# Modular_RFPA_RevB.net
KiCad netlist of a schematic drawn in EAGLE
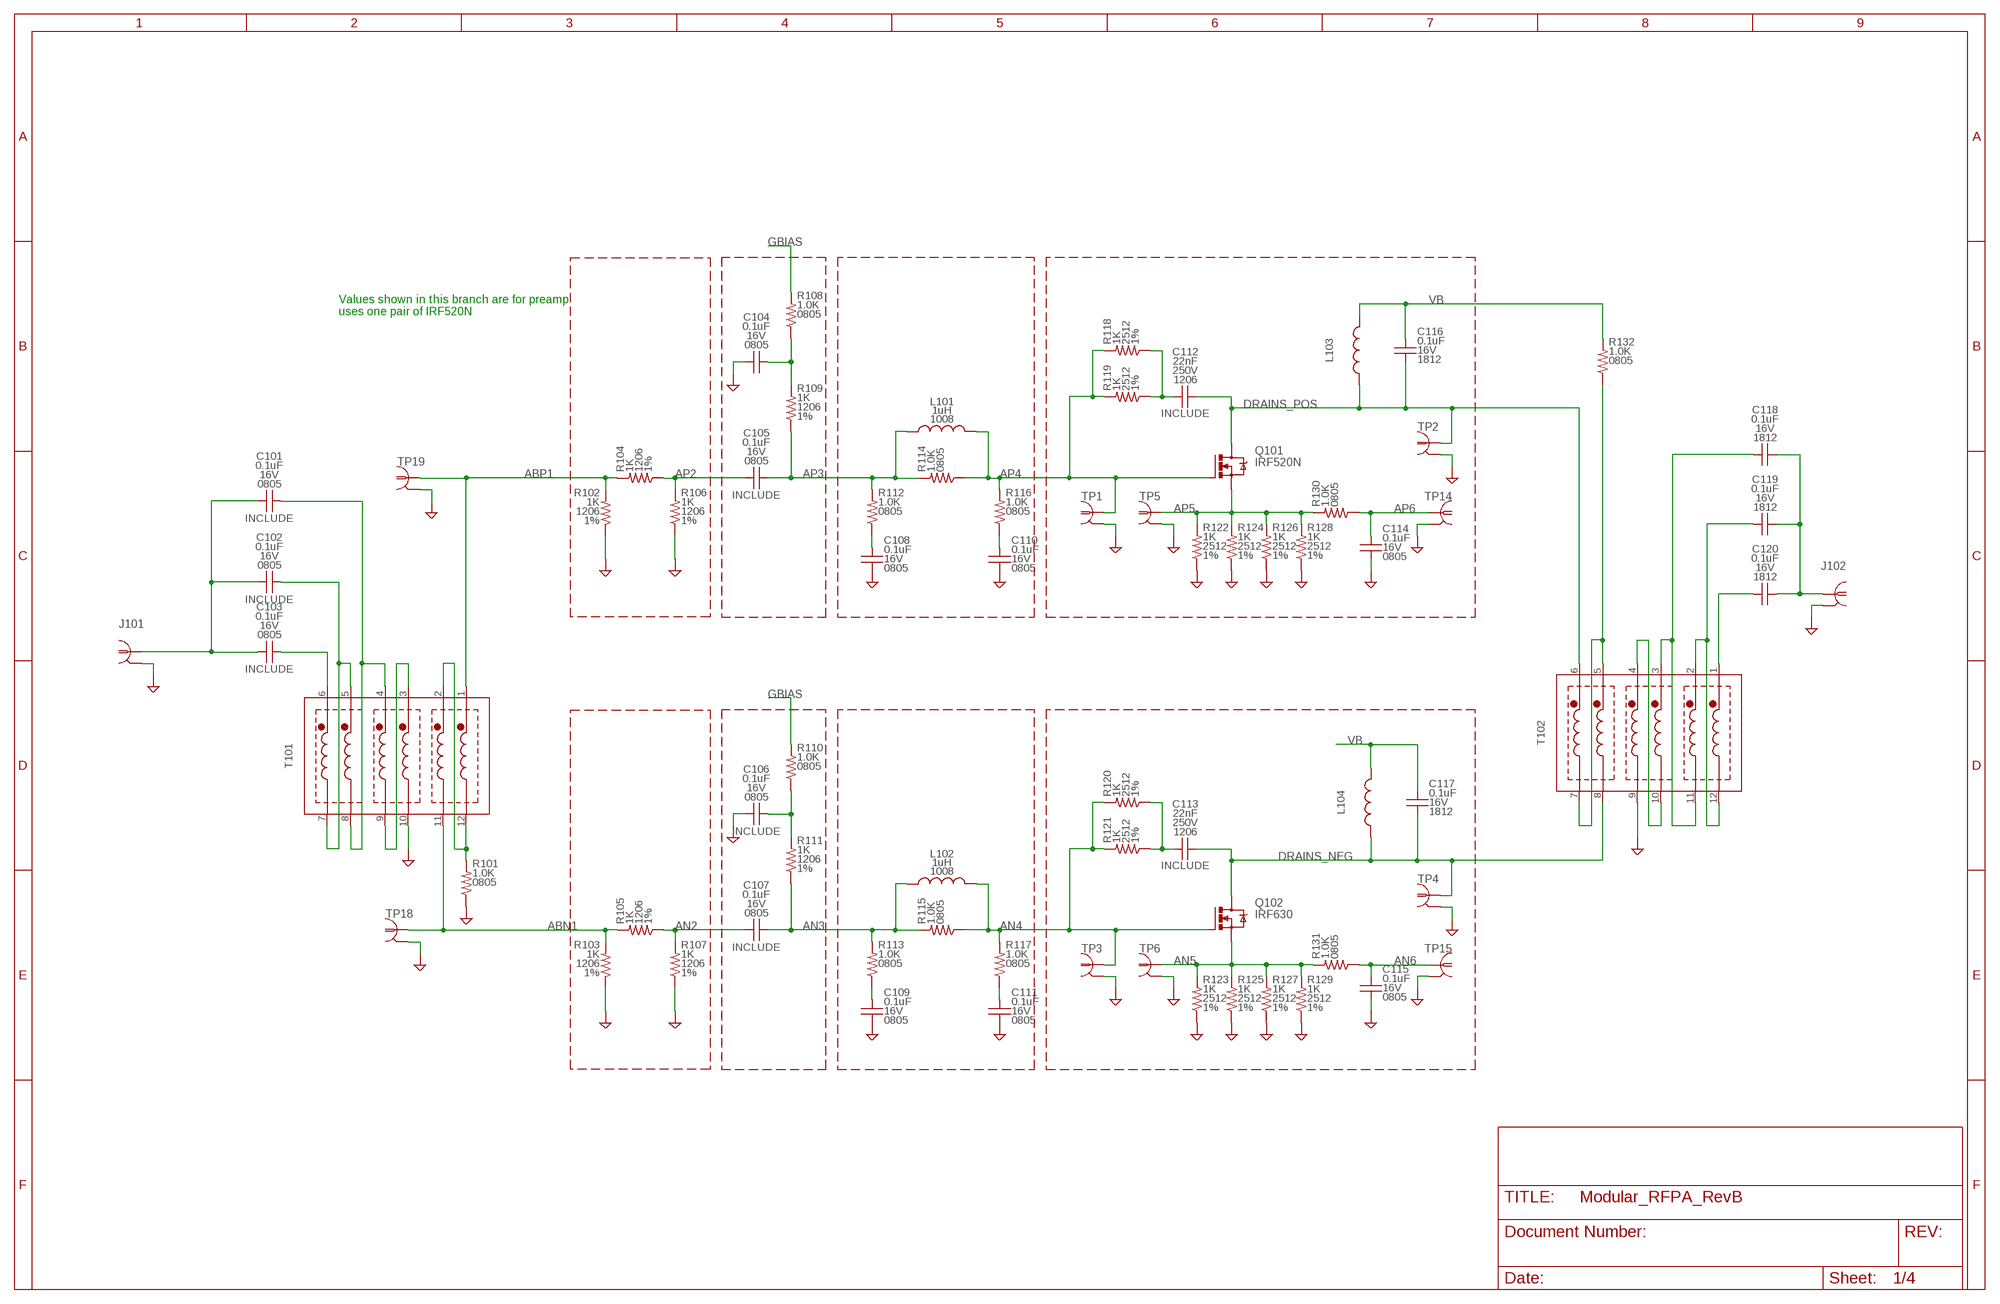
[diagram p0: schematic, sheet 1, part 1 of 2]
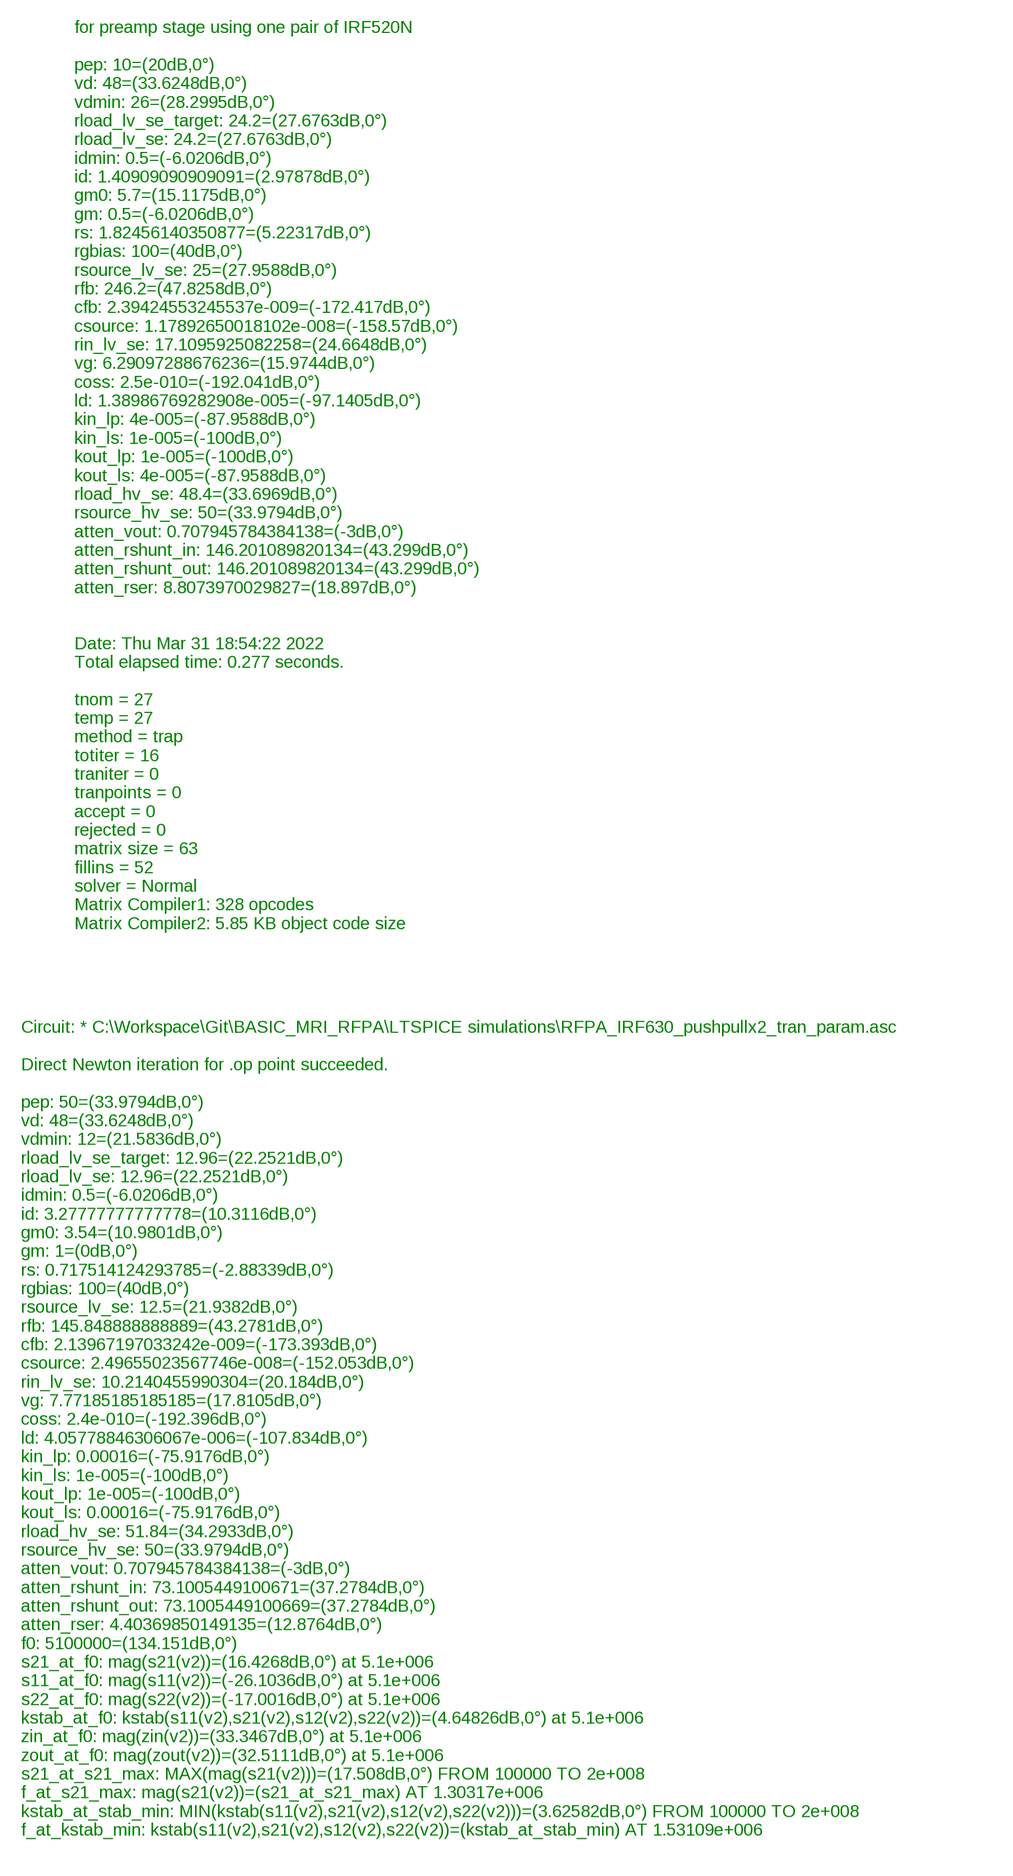
[diagram p1: schematic, sheet 1, part 2 of 2]
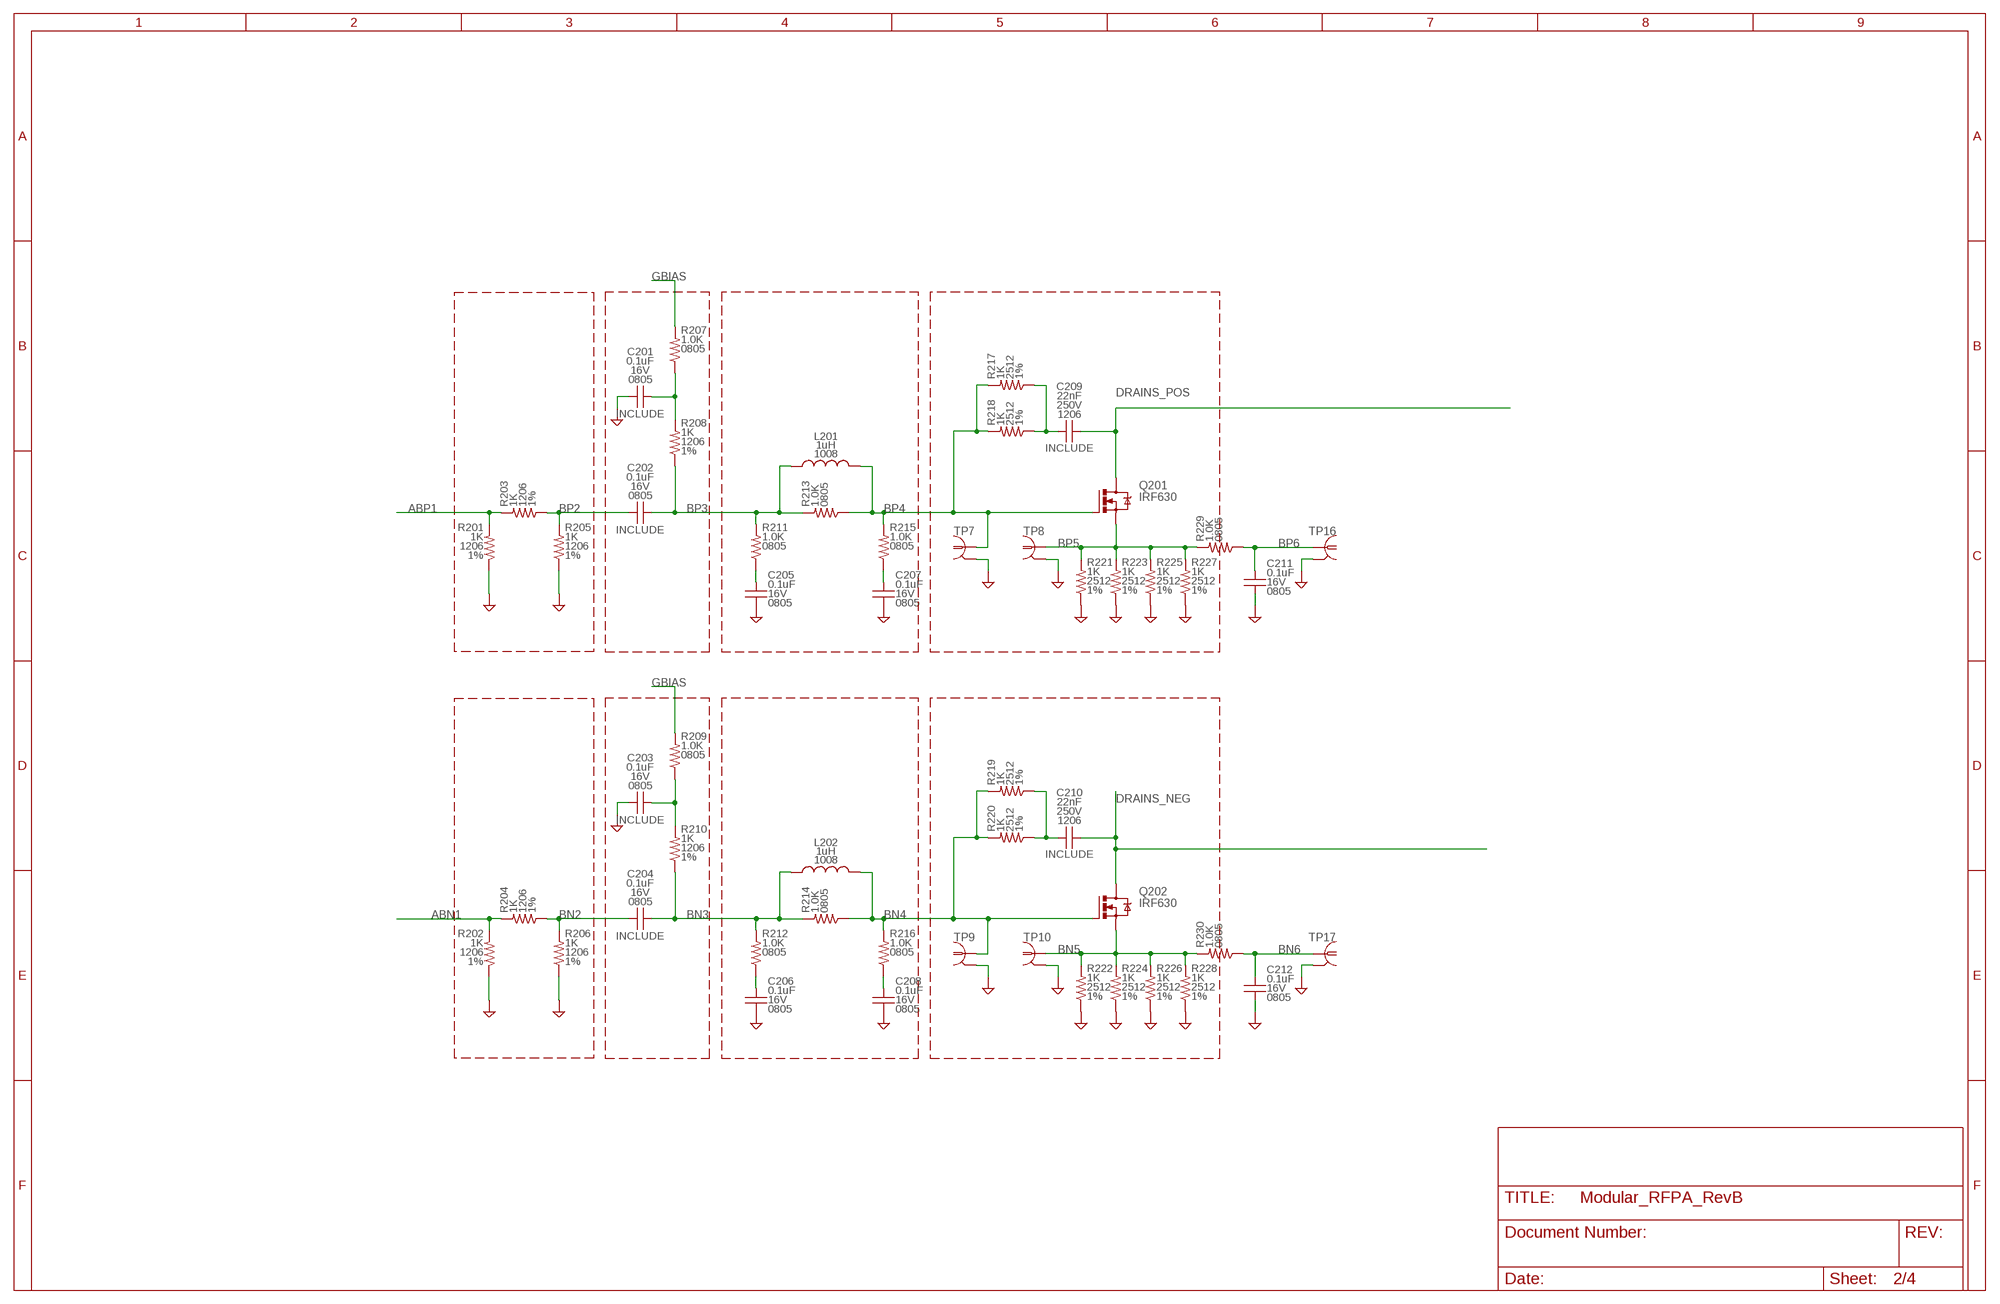
[diagram p2: schematic, sheet 2]
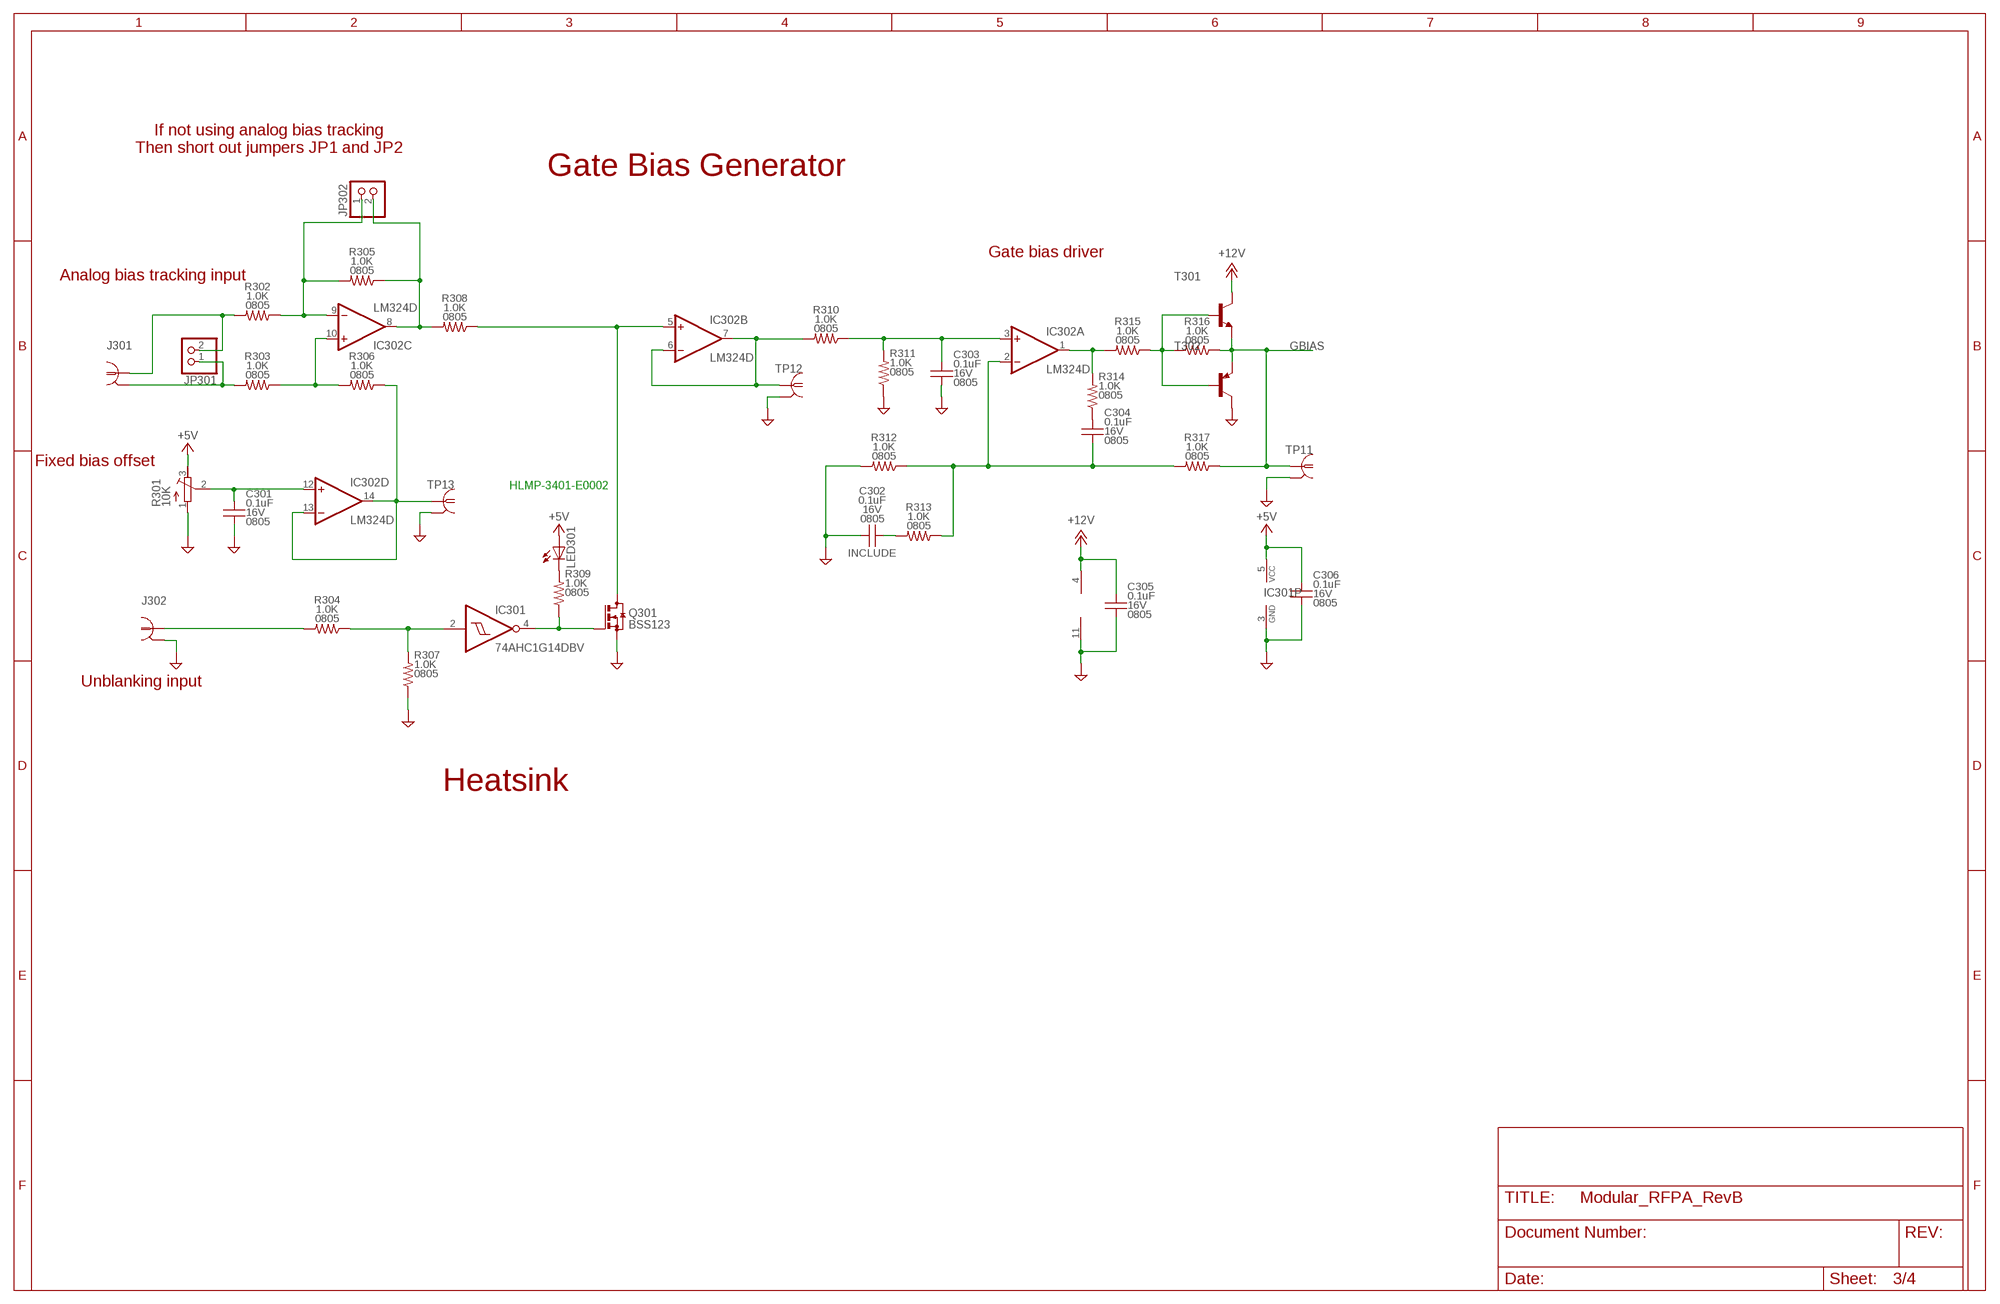
[diagram p3: schematic, sheet 3]
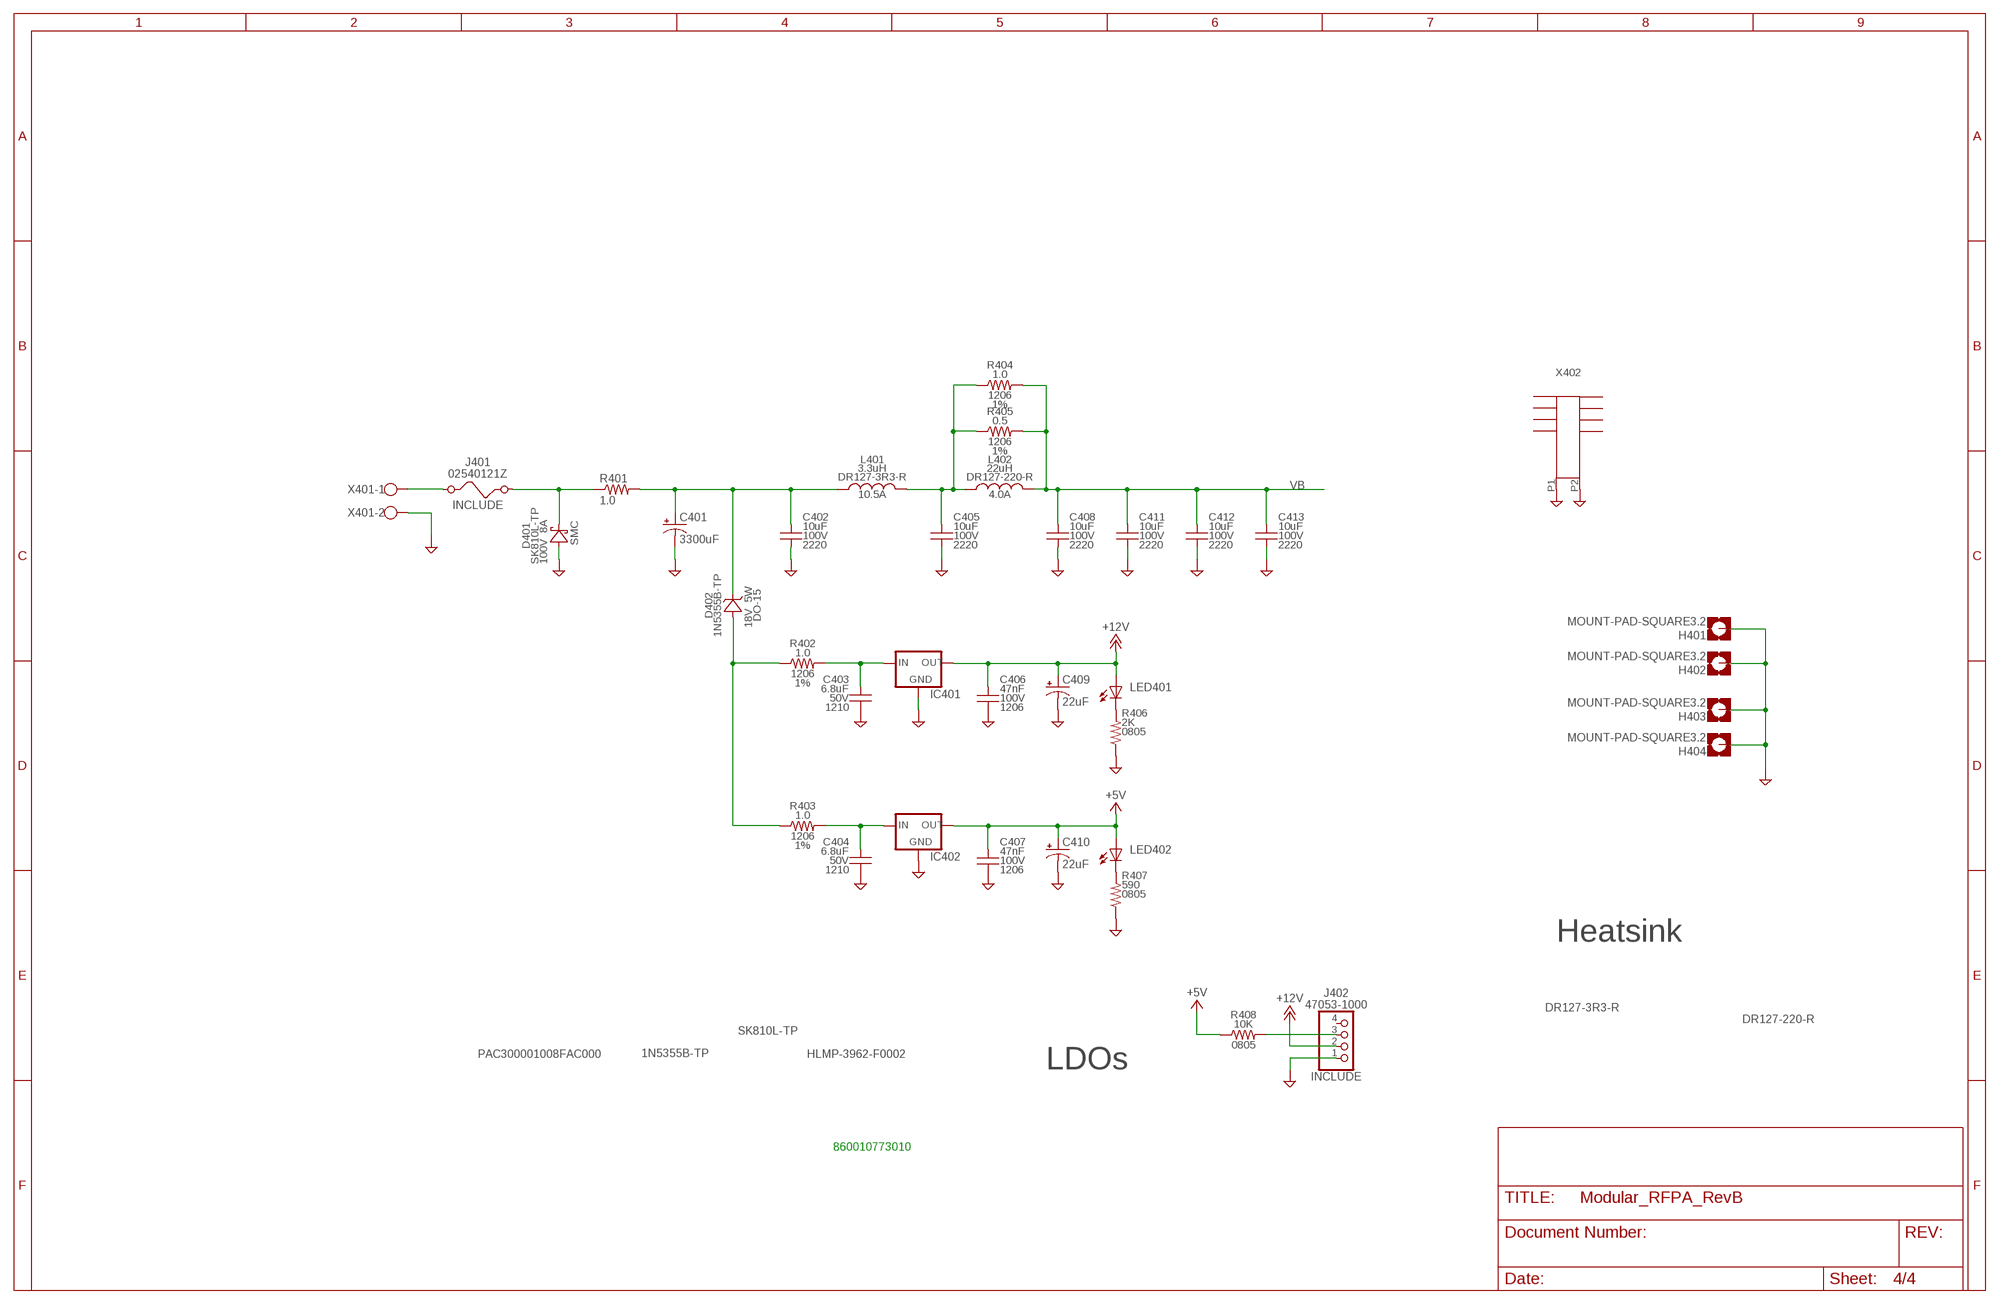
[diagram p4: schematic, sheet 4]

(export (version "E")
  (design (tool "Eeschema 10.0.6"))
  (components
    (comp (ref "C401")
      (value "3300uF")
      (footprint "eagle-import:EB25D")
      (libsource (lib "eagle-import") (part "CPOL-USE10-25"))
    )
    (comp (ref "C402")
      (value "10uF")
      (footprint "eagle-import:C2220_CKG57N")
      (fields
        (field (name "BOM") "INCLUDE")
        (field (name "PACKAGE") "2220")
        (field (name "PARTNO") "CGA9N3X7S2A106M230KE")
        (field (name "VOLTAGE") "100V")
      )
      (libsource (lib "eagle-import") (part "CC2220_CKG57NCC-10U-100V-20%-2220-X7T"))
    )
    (comp (ref "C403")
      (value "6.8uF")
      (footprint "eagle-import:C1210")
      (fields (field (name "PARTNO") "CGA6P3X7S1H685K250AB") (field (name "VOLTAGE") "50V"))
      (libsource (lib "eagle-import") (part "CC1210CC-6.8U-50V-10%-1210-X7S"))
    )
    (comp (ref "C404")
      (value "6.8uF")
      (footprint "eagle-import:C1210")
      (fields (field (name "PARTNO") "CGA6P3X7S1H685K250AB") (field (name "VOLTAGE") "50V"))
      (libsource (lib "eagle-import") (part "CC1210CC-6.8U-50V-10%-1210-X7S"))
    )
    (comp (ref "C405")
      (value "10uF")
      (footprint "eagle-import:C2220_CKG57N")
      (fields
        (field (name "BOM") "INCLUDE")
        (field (name "PACKAGE") "2220")
        (field (name "PARTNO") "CGA9N3X7S2A106M230KE")
        (field (name "VOLTAGE") "100V")
      )
      (libsource (lib "eagle-import") (part "CC2220_CKG57NCC-10U-100V-20%-2220-X7T"))
    )
    (comp (ref "C406")
      (value "47nF")
      (footprint "eagle-import:C1206")
      (fields (field (name "PARTNO") "C3216C0G2A473J115AC") (field (name "VOLTAGE") "100V"))
      (libsource (lib "eagle-import") (part "CC1206C-47N-100V-5%-1206-NP0"))
    )
    (comp (ref "C407")
      (value "47nF")
      (footprint "eagle-import:C1206")
      (fields (field (name "PARTNO") "C3216C0G2A473J115AC") (field (name "VOLTAGE") "100V"))
      (libsource (lib "eagle-import") (part "CC1206C-47N-100V-5%-1206-NP0"))
    )
    (comp (ref "C408")
      (value "10uF")
      (footprint "eagle-import:C2220_CKG57N")
      (fields (field (name "PARTNO") "CGA9N3X7S2A106M230KE") (field (name "VOLTAGE") "100V"))
      (libsource (lib "eagle-import") (part "CC2220_CKG57NCC-10U-100V-20%-2220-X7T"))
    )
    (comp (ref "C409")
      (value "22uF")
      (footprint "eagle-import:E2,5-7")
      (libsource (lib "eagle-import") (part "CPOL-USE2.5-7"))
    )
    (comp (ref "C410")
      (value "22uF")
      (footprint "eagle-import:E2,5-7")
      (libsource (lib "eagle-import") (part "CPOL-USE2.5-7"))
    )
    (comp (ref "C411")
      (value "10uF")
      (footprint "eagle-import:C2220_CKG57N")
      (fields (field (name "PARTNO") "CGA9N3X7S2A106M230KE") (field (name "VOLTAGE") "100V"))
      (libsource (lib "eagle-import") (part "CC2220_CKG57NCC-10U-100V-20%-2220-X7T"))
    )
    (comp (ref "C412")
      (value "10uF")
      (footprint "eagle-import:C2220_CKG57N")
      (fields (field (name "PARTNO") "CGA9N3X7S2A106M230KE") (field (name "VOLTAGE") "100V"))
      (libsource (lib "eagle-import") (part "CC2220_CKG57NCC-10U-100V-20%-2220-X7T"))
    )
    (comp (ref "C413")
      (value "10uF")
      (footprint "eagle-import:C2220_CKG57N")
      (fields (field (name "PARTNO") "CGA9N3X7S2A106M230KE") (field (name "VOLTAGE") "100V"))
      (libsource (lib "eagle-import") (part "CC2220_CKG57NCC-10U-100V-20%-2220-X7T"))
    )
    (comp (ref "D401")
      (value "D-SCHOTTKYSK810L-TPSMC")
      (footprint "eagle-import:DO-214AB(SMC)")
      (fields (field (name "PARTNO") "SK810L-TP") (field (name "VOLTAGE") "100V"))
      (libsource (lib "eagle-import") (part "D-SCHOTTKYSMCSK810L-TP"))
    )
    (comp (ref "D402")
      (value "D-ZENER1N5355B-TPDO15-12")
      (footprint "eagle-import:DO15-12")
      (fields (field (name "PARTNO") "1N5355B-TP") (field (name "POWER") "5W") (field (name "VOLTAGE") "18V"))
      (libsource (lib "eagle-import") (part "D-ZENERDO15-121N5355B-TP"))
    )
    (comp (ref "H401")
      (value "MOUNT-PAD-SQUARE3.2")
      (footprint "eagle-import:3,2-PAD-SQUARE")
      (libsource (lib "eagle-import") (part "MOUNT-PAD-SQUARE3.2"))
    )
    (comp (ref "H402")
      (value "MOUNT-PAD-SQUARE3.2")
      (footprint "eagle-import:3,2-PAD-SQUARE")
      (libsource (lib "eagle-import") (part "MOUNT-PAD-SQUARE3.2"))
    )
    (comp (ref "H403")
      (value "MOUNT-PAD-SQUARE3.2")
      (footprint "eagle-import:3,2-PAD-SQUARE")
      (libsource (lib "eagle-import") (part "MOUNT-PAD-SQUARE3.2"))
    )
    (comp (ref "H404")
      (value "MOUNT-PAD-SQUARE3.2")
      (footprint "eagle-import:3,2-PAD-SQUARE")
      (libsource (lib "eagle-import") (part "MOUNT-PAD-SQUARE3.2"))
    )
    (comp (ref "IC401")
      (value "78XXS")
      (footprint "eagle-import:78XXS")
      (libsource (lib "eagle-import") (part "78XXS"))
    )
    (comp (ref "IC402")
      (value "78XXS")
      (footprint "eagle-import:78XXS")
      (libsource (lib "eagle-import") (part "78XXS"))
    )
    (comp (ref "J401")
      (value "FUSE_2P")
      (footprint "eagle-import:02540121Z")
      (fields (field (name "PARTNO") "02540121Z"))
      (libsource (lib "eagle-import") (part "FUSE_2P"))
    )
    (comp (ref "J402")
      (value "KK_PCFAN")
      (footprint "eagle-import:47053-1000")
      (fields (field (name "PARTNO") "47053-1000"))
      (libsource (lib "eagle-import") (part "KK_PCFAN"))
    )
    (comp (ref "L401")
      (value "3.3uH")
      (footprint "eagle-import:DR127")
      (fields (field (name "PARTNO") "DR127-3R3-R"))
      (libsource (lib "eagle-import") (part "LL-3.3U-FERRITE-20%-12.5X12.5MM-10.5A"))
    )
    (comp (ref "L402")
      (value "22uH")
      (footprint "eagle-import:DR127")
      (fields (field (name "PARTNO") "DR127-220-R"))
      (libsource (lib "eagle-import") (part "LL-22U-FERRITE-20%-12.5X12.5MM-4A"))
    )
    (comp (ref "LED401")
      (value "LED5MM")
      (footprint "eagle-import:LED5MM")
      (libsource (lib "eagle-import") (part "LED5MM"))
    )
    (comp (ref "LED402")
      (value "LED5MM")
      (footprint "eagle-import:LED5MM")
      (libsource (lib "eagle-import") (part "LED5MM"))
    )
    (comp (ref "R401")
      (value "1.0")
      (footprint "eagle-import:P0817V")
      (libsource (lib "eagle-import") (part "R-US_0817/7V"))
    )
    (comp (ref "R402")
      (value "1.0")
      (footprint "eagle-import:R1206")
      (fields (field (name "POWER") "0.25"))
      (libsource (lib "eagle-import") (part "R90R1206R-1.0K-1%-1206-0.25W"))
    )
    (comp (ref "R403")
      (value "1.0")
      (footprint "eagle-import:R1206")
      (fields (field (name "POWER") "0.25"))
      (libsource (lib "eagle-import") (part "R90R1206R-1.0K-1%-1206-0.25W"))
    )
    (comp (ref "R404")
      (value "1.0")
      (footprint "eagle-import:R1206")
      (fields (field (name "POWER") "0.25"))
      (libsource (lib "eagle-import") (part "R90R1206R-1.0K-1%-1206-0.25W"))
    )
    (comp (ref "R405")
      (value "0.5")
      (footprint "eagle-import:R1206")
      (fields (field (name "POWER") "0.25"))
      (libsource (lib "eagle-import") (part "R90R1206R-1.0K-1%-1206-0.25W"))
    )
    (comp (ref "R406")
      (value "2K")
      (footprint "eagle-import:0805_IPC-7351B")
      (libsource (lib "eagle-import") (part "R0805_IPCR-1.0K-0.1%-0805-0.1W"))
    )
    (comp (ref "R407")
      (value "590")
      (footprint "eagle-import:0805_IPC-7351B")
      (libsource (lib "eagle-import") (part "R0805_IPCR-1.0K-0.1%-0805-0.1W"))
    )
    (comp (ref "R408")
      (value "10K")
      (footprint "eagle-import:0805_IPC-7351B")
      (libsource (lib "eagle-import") (part "R900805_IPCR-1.0K-0.1%-0805-0.1W"))
    )
    (comp (ref "X401")
      (value "W237-102")
      (footprint "eagle-import:W237-102")
      (fields (field (name "MPN") "237-102"))
      (libsource (lib "eagle-import") (part "W237-102"))
    )
    (comp (ref "X402")
      (value "HEATSINK_OMNI_DUAL30-75-D")
      (footprint "eagle-import:OMNI-UNI-30-75-D")
      (libsource (lib "eagle-import") (part "HEATSINK_OMNI_DUAL30-75-D"))
    )
    (comp (ref "C201")
      (value "0.1uF")
      (footprint "eagle-import:0805_IPC-7351B")
      (fields (field (name "PACKAGE") "0805") (field (name "VOLTAGE") "16V") (field (name "BOM") "INCLUDE"))
      (libsource (lib "eagle-import") (part "C0805_IPCC-0.1U-16V-0805-X7R"))
    )
    (comp (ref "C202")
      (value "0.1uF")
      (footprint "eagle-import:0805_IPC-7351B")
      (fields (field (name "PACKAGE") "0805") (field (name "VOLTAGE") "16V") (field (name "BOM") "INCLUDE"))
      (libsource (lib "eagle-import") (part "C0805_IPCC-0.1U-16V-0805-X7R"))
    )
    (comp (ref "C203")
      (value "0.1uF")
      (footprint "eagle-import:0805_IPC-7351B")
      (fields (field (name "PACKAGE") "0805") (field (name "VOLTAGE") "16V") (field (name "BOM") "INCLUDE"))
      (libsource (lib "eagle-import") (part "C0805_IPCC-0.1U-16V-0805-X7R"))
    )
    (comp (ref "C204")
      (value "0.1uF")
      (footprint "eagle-import:0805_IPC-7351B")
      (fields (field (name "PACKAGE") "0805") (field (name "VOLTAGE") "16V") (field (name "BOM") "INCLUDE"))
      (libsource (lib "eagle-import") (part "C0805_IPCC-0.1U-16V-0805-X7R"))
    )
    (comp (ref "C205")
      (value "0.1uF")
      (footprint "eagle-import:0805_IPC-7351B")
      (fields (field (name "VOLTAGE") "16V"))
      (libsource (lib "eagle-import") (part "C0805_IPCC-0.1U-16V-0805-X7R"))
    )
    (comp (ref "C206")
      (value "0.1uF")
      (footprint "eagle-import:0805_IPC-7351B")
      (fields (field (name "VOLTAGE") "16V"))
      (libsource (lib "eagle-import") (part "C0805_IPCC-0.1U-16V-0805-X7R"))
    )
    (comp (ref "C207")
      (value "0.1uF")
      (footprint "eagle-import:0805_IPC-7351B")
      (fields (field (name "VOLTAGE") "16V"))
      (libsource (lib "eagle-import") (part "C0805_IPCC-0.1U-16V-0805-X7R"))
    )
    (comp (ref "C208")
      (value "0.1uF")
      (footprint "eagle-import:0805_IPC-7351B")
      (fields (field (name "VOLTAGE") "16V"))
      (libsource (lib "eagle-import") (part "C0805_IPCC-0.1U-16V-0805-X7R"))
    )
    (comp (ref "C209")
      (value "22nF")
      (footprint "eagle-import:C1206")
      (fields
        (field (name "BOM") "INCLUDE")
        (field (name "PACKAGE") "1206")
        (field (name "PARTNO") "C3216NP02E223J160AA")
        (field (name "VOLTAGE") "250V")
      )
      (libsource (lib "eagle-import") (part "CC1206C-22N-250V-5%-1206-NP0"))
    )
    (comp (ref "C210")
      (value "22nF")
      (footprint "eagle-import:C1206")
      (fields
        (field (name "BOM") "INCLUDE")
        (field (name "PACKAGE") "1206")
        (field (name "PARTNO") "C3216NP02E223J160AA")
        (field (name "VOLTAGE") "250V")
      )
      (libsource (lib "eagle-import") (part "CC1206C-22N-250V-5%-1206-NP0"))
    )
    (comp (ref "C211")
      (value "0.1uF")
      (footprint "eagle-import:0805_IPC-7351B")
      (fields (field (name "VOLTAGE") "16V"))
      (libsource (lib "eagle-import") (part "C0805_IPCC-0.1U-16V-0805-X7R"))
    )
    (comp (ref "C212")
      (value "0.1uF")
      (footprint "eagle-import:0805_IPC-7351B")
      (fields (field (name "VOLTAGE") "16V"))
      (libsource (lib "eagle-import") (part "C0805_IPCC-0.1U-16V-0805-X7R"))
    )
    (comp (ref "L201")
      (value "1uH")
      (footprint "eagle-import:L1008")
      (fields (field (name "PARTNO") "1008CS-102XJEC"))
      (libsource (lib "eagle-import") (part "L_CHIP1008L-1.0U-AIR-5%-1008-0.37A"))
    )
    (comp (ref "L202")
      (value "1uH")
      (footprint "eagle-import:L1008")
      (fields (field (name "PARTNO") "1008CS-102XJEC"))
      (libsource (lib "eagle-import") (part "L_CHIP1008L-1.0U-AIR-5%-1008-0.37A"))
    )
    (comp (ref "Q201")
      (value "IRF630")
      (footprint "eagle-import:TO220BV")
      (libsource (lib "eagle-import") (part "IRF540"))
    )
    (comp (ref "Q202")
      (value "IRF630")
      (footprint "eagle-import:TO220BV")
      (libsource (lib "eagle-import") (part "IRF540"))
    )
    (comp (ref "R201")
      (value "1K")
      (footprint "eagle-import:R1206")
      (fields (field (name "POWER") "0.25"))
      (libsource (lib "eagle-import") (part "RR1206R-1.0K-1%-1206-0.25W"))
    )
    (comp (ref "R202")
      (value "1K")
      (footprint "eagle-import:R1206")
      (fields (field (name "POWER") "0.25"))
      (libsource (lib "eagle-import") (part "RR1206R-1.0K-1%-1206-0.25W"))
    )
    (comp (ref "R203")
      (value "1K")
      (footprint "eagle-import:R1206")
      (fields (field (name "POWER") "0.25"))
      (libsource (lib "eagle-import") (part "RR1206R-1.0K-1%-1206-0.25W"))
    )
    (comp (ref "R204")
      (value "1K")
      (footprint "eagle-import:R1206")
      (fields (field (name "POWER") "0.25"))
      (libsource (lib "eagle-import") (part "RR1206R-1.0K-1%-1206-0.25W"))
    )
    (comp (ref "R205")
      (value "1K")
      (footprint "eagle-import:R1206")
      (fields (field (name "POWER") "0.25"))
      (libsource (lib "eagle-import") (part "RR1206R-1.0K-1%-1206-0.25W"))
    )
    (comp (ref "R206")
      (value "1K")
      (footprint "eagle-import:R1206")
      (fields (field (name "POWER") "0.25"))
      (libsource (lib "eagle-import") (part "RR1206R-1.0K-1%-1206-0.25W"))
    )
    (comp (ref "R207")
      (value "1.0K")
      (footprint "eagle-import:0805_IPC-7351B")
      (libsource (lib "eagle-import") (part "R0805_IPCR-1.0K-0.1%-0805-0.1W"))
    )
    (comp (ref "R208")
      (value "1K")
      (footprint "eagle-import:R1206")
      (fields (field (name "POWER") "0.25"))
      (libsource (lib "eagle-import") (part "RR1206R-1.0K-1%-1206-0.25W"))
    )
    (comp (ref "R209")
      (value "1.0K")
      (footprint "eagle-import:0805_IPC-7351B")
      (libsource (lib "eagle-import") (part "R0805_IPCR-1.0K-0.1%-0805-0.1W"))
    )
    (comp (ref "R210")
      (value "1K")
      (footprint "eagle-import:R1206")
      (fields (field (name "POWER") "0.25"))
      (libsource (lib "eagle-import") (part "RR1206R-1.0K-1%-1206-0.25W"))
    )
    (comp (ref "R211")
      (value "1.0K")
      (footprint "eagle-import:0805_IPC-7351B")
      (libsource (lib "eagle-import") (part "R0805_IPCR-1.0K-0.1%-0805-0.1W"))
    )
    (comp (ref "R212")
      (value "1.0K")
      (footprint "eagle-import:0805_IPC-7351B")
      (libsource (lib "eagle-import") (part "R0805_IPCR-1.0K-0.1%-0805-0.1W"))
    )
    (comp (ref "R213")
      (value "1.0K")
      (footprint "eagle-import:0805_IPC-7351B")
      (libsource (lib "eagle-import") (part "R0805_IPCR-1.0K-0.1%-0805-0.1W"))
    )
    (comp (ref "R214")
      (value "1.0K")
      (footprint "eagle-import:0805_IPC-7351B")
      (libsource (lib "eagle-import") (part "R0805_IPCR-1.0K-0.1%-0805-0.1W"))
    )
    (comp (ref "R215")
      (value "1.0K")
      (footprint "eagle-import:0805_IPC-7351B")
      (libsource (lib "eagle-import") (part "R0805_IPCR-1.0K-0.1%-0805-0.1W"))
    )
    (comp (ref "R216")
      (value "1.0K")
      (footprint "eagle-import:0805_IPC-7351B")
      (libsource (lib "eagle-import") (part "R0805_IPCR-1.0K-0.1%-0805-0.1W"))
    )
    (comp (ref "R217")
      (value "1K")
      (footprint "eagle-import:R2512")
      (fields (field (name "POWER") "1"))
      (libsource (lib "eagle-import") (part "RR2512R-1K-1%-2512-1W"))
    )
    (comp (ref "R218")
      (value "1K")
      (footprint "eagle-import:R2512")
      (fields (field (name "POWER") "1"))
      (libsource (lib "eagle-import") (part "RR2512R-1K-1%-2512-1W"))
    )
    (comp (ref "R219")
      (value "1K")
      (footprint "eagle-import:R2512")
      (fields (field (name "POWER") "1"))
      (libsource (lib "eagle-import") (part "RR2512R-1K-1%-2512-1W"))
    )
    (comp (ref "R220")
      (value "1K")
      (footprint "eagle-import:R2512")
      (fields (field (name "POWER") "1"))
      (libsource (lib "eagle-import") (part "RR2512R-1K-1%-2512-1W"))
    )
    (comp (ref "R221")
      (value "1K")
      (footprint "eagle-import:R2512")
      (fields (field (name "POWER") "1"))
      (libsource (lib "eagle-import") (part "RR2512R-1K-1%-2512-1W"))
    )
    (comp (ref "R222")
      (value "1K")
      (footprint "eagle-import:R2512")
      (fields (field (name "POWER") "1"))
      (libsource (lib "eagle-import") (part "RR2512R-1K-1%-2512-1W"))
    )
    (comp (ref "R223")
      (value "1K")
      (footprint "eagle-import:R2512")
      (fields (field (name "POWER") "1"))
      (libsource (lib "eagle-import") (part "RR2512R-1K-1%-2512-1W"))
    )
    (comp (ref "R224")
      (value "1K")
      (footprint "eagle-import:R2512")
      (fields (field (name "POWER") "1"))
      (libsource (lib "eagle-import") (part "RR2512R-1K-1%-2512-1W"))
    )
    (comp (ref "R225")
      (value "1K")
      (footprint "eagle-import:R2512")
      (fields (field (name "POWER") "1"))
      (libsource (lib "eagle-import") (part "RR2512R-1K-1%-2512-1W"))
    )
    (comp (ref "R226")
      (value "1K")
      (footprint "eagle-import:R2512")
      (fields (field (name "POWER") "1"))
      (libsource (lib "eagle-import") (part "RR2512R-1K-1%-2512-1W"))
    )
    (comp (ref "R227")
      (value "1K")
      (footprint "eagle-import:R2512")
      (fields (field (name "POWER") "1"))
      (libsource (lib "eagle-import") (part "RR2512R-1K-1%-2512-1W"))
    )
    (comp (ref "R228")
      (value "1K")
      (footprint "eagle-import:R2512")
      (fields (field (name "POWER") "1"))
      (libsource (lib "eagle-import") (part "RR2512R-1K-1%-2512-1W"))
    )
    (comp (ref "R229")
      (value "1.0K")
      (footprint "eagle-import:0805_IPC-7351B")
      (libsource (lib "eagle-import") (part "R0805_IPCR-1.0K-0.1%-0805-0.1W"))
    )
    (comp (ref "R230")
      (value "1.0K")
      (footprint "eagle-import:0805_IPC-7351B")
      (libsource (lib "eagle-import") (part "R0805_IPCR-1.0K-0.1%-0805-0.1W"))
    )
    (comp (ref "TP7")
      (value "PROBE_TPTP_5MM")
      (footprint "eagle-import:PROBE_TP_5MM")
      (libsource (lib "eagle-import") (part "PROBE_TPTP_5MM"))
    )
    (comp (ref "TP8")
      (value "PROBE_TPTP_7P5MM")
      (footprint "eagle-import:PROBE_TP_7P5MM")
      (libsource (lib "eagle-import") (part "PROBE_TPTP_7P5MM"))
    )
    (comp (ref "TP9")
      (value "PROBE_TPTP_5MM")
      (footprint "eagle-import:PROBE_TP_5MM")
      (libsource (lib "eagle-import") (part "PROBE_TPTP_5MM"))
    )
    (comp (ref "TP10")
      (value "PROBE_TPTP_5MM")
      (footprint "eagle-import:PROBE_TP_5MM")
      (libsource (lib "eagle-import") (part "PROBE_TPTP_5MM"))
    )
    (comp (ref "TP16")
      (value "PROBE_TPTP_5MM")
      (footprint "eagle-import:PROBE_TP_5MM")
      (libsource (lib "eagle-import") (part "PROBE_TPTP_5MM"))
    )
    (comp (ref "TP17")
      (value "PROBE_TPTP_7P5MM")
      (footprint "eagle-import:PROBE_TP_7P5MM")
      (libsource (lib "eagle-import") (part "PROBE_TPTP_7P5MM"))
    )
    (comp (ref "C301")
      (value "0.1uF")
      (footprint "eagle-import:0805_IPC-7351B")
      (fields (field (name "VOLTAGE") "16V"))
      (libsource (lib "eagle-import") (part "C0805_IPCC-0.1U-16V-0805-X7R"))
    )
    (comp (ref "C302")
      (value "0.1uF")
      (footprint "eagle-import:0805_IPC-7351B")
      (fields (field (name "PACKAGE") "0805") (field (name "VOLTAGE") "16V") (field (name "BOM") "INCLUDE"))
      (libsource (lib "eagle-import") (part "C0805_IPCC-0.1U-16V-0805-X7R"))
    )
    (comp (ref "C303")
      (value "0.1uF")
      (footprint "eagle-import:0805_IPC-7351B")
      (fields (field (name "VOLTAGE") "16V"))
      (libsource (lib "eagle-import") (part "C0805_IPCC-0.1U-16V-0805-X7R"))
    )
    (comp (ref "C304")
      (value "0.1uF")
      (footprint "eagle-import:0805_IPC-7351B")
      (fields (field (name "VOLTAGE") "16V"))
      (libsource (lib "eagle-import") (part "C0805_IPCC-0.1U-16V-0805-X7R"))
    )
    (comp (ref "C305")
      (value "0.1uF")
      (footprint "eagle-import:0805_IPC-7351B")
      (fields (field (name "VOLTAGE") "16V"))
      (libsource (lib "eagle-import") (part "C0805_IPCC-0.1U-16V-0805-X7R"))
    )
    (comp (ref "C306")
      (value "0.1uF")
      (footprint "eagle-import:0805_IPC-7351B")
      (fields (field (name "VOLTAGE") "16V"))
      (libsource (lib "eagle-import") (part "C0805_IPCC-0.1U-16V-0805-X7R"))
    )
    (comp (ref "IC301")
      (value "74AHC1G14DBV")
      (footprint "eagle-import:SOT23-5")
      (libsource (lib "eagle-import") (part "741G14DBVAHC"))
    )
    (comp (ref "IC302")
      (value "LM324D")
      (footprint "eagle-import:SO14")
      (libsource (lib "eagle-import") (part "LM324D"))
    )
    (comp (ref "J301")
      (value "COAXBNC_EDGE")
      (footprint "eagle-import:BNC_EDGE")
      (libsource (lib "eagle-import") (part "COAXBNC_EDGE"))
    )
    (comp (ref "J302")
      (value "COAXBNC_EDGE")
      (footprint "eagle-import:BNC_EDGE")
      (libsource (lib "eagle-import") (part "COAXBNC_EDGE"))
    )
    (comp (ref "JP301")
      (value "PINHD-1X2")
      (footprint "eagle-import:1X02")
      (libsource (lib "eagle-import") (part "PINHD-1X2"))
    )
    (comp (ref "JP302")
      (value "PINHD-1X2")
      (footprint "eagle-import:1X02")
      (libsource (lib "eagle-import") (part "PINHD-1X2"))
    )
    (comp (ref "LED301")
      (value "LED5MM")
      (footprint "eagle-import:LED5MM")
      (libsource (lib "eagle-import") (part "LED5MM"))
    )
    (comp (ref "Q301")
      (value "BSS123")
      (footprint "eagle-import:SOT23")
      (libsource (lib "eagle-import") (part "BSS123"))
    )
    (comp (ref "R301")
      (value "10K")
      (footprint "eagle-import:RTRIM3299W")
      (libsource (lib "eagle-import") (part "R-TRIMM3299W"))
    )
    (comp (ref "R302")
      (value "1.0K")
      (footprint "eagle-import:0805_IPC-7351B")
      (fields (field (name "PACKAGE") "0805"))
      (libsource (lib "eagle-import") (part "R0805_IPCR-1.0K-0.1%-0805-0.1W"))
    )
    (comp (ref "R303")
      (value "1.0K")
      (footprint "eagle-import:0805_IPC-7351B")
      (fields (field (name "PACKAGE") "0805"))
      (libsource (lib "eagle-import") (part "R0805_IPCR-1.0K-0.1%-0805-0.1W"))
    )
    (comp (ref "R304")
      (value "1.0K")
      (footprint "eagle-import:0805_IPC-7351B")
      (fields (field (name "PACKAGE") "0805"))
      (libsource (lib "eagle-import") (part "R0805_IPCR-1.0K-0.1%-0805-0.1W"))
    )
    (comp (ref "R305")
      (value "1.0K")
      (footprint "eagle-import:0805_IPC-7351B")
      (fields (field (name "PACKAGE") "0805"))
      (libsource (lib "eagle-import") (part "R0805_IPCR-1.0K-0.1%-0805-0.1W"))
    )
    (comp (ref "R306")
      (value "1.0K")
      (footprint "eagle-import:0805_IPC-7351B")
      (fields (field (name "PACKAGE") "0805"))
      (libsource (lib "eagle-import") (part "R0805_IPCR-1.0K-0.1%-0805-0.1W"))
    )
    (comp (ref "R307")
      (value "1.0K")
      (footprint "eagle-import:0805_IPC-7351B")
      (libsource (lib "eagle-import") (part "R0805_IPCR-1.0K-0.1%-0805-0.1W"))
    )
    (comp (ref "R308")
      (value "1.0K")
      (footprint "eagle-import:0805_IPC-7351B")
      (fields (field (name "PACKAGE") "0805"))
      (libsource (lib "eagle-import") (part "R0805_IPCR-1.0K-0.1%-0805-0.1W"))
    )
    (comp (ref "R309")
      (value "1.0K")
      (footprint "eagle-import:0805_IPC-7351B")
      (libsource (lib "eagle-import") (part "R0805_IPCR-1.0K-0.1%-0805-0.1W"))
    )
    (comp (ref "R310")
      (value "1.0K")
      (footprint "eagle-import:0805_IPC-7351B")
      (fields (field (name "PACKAGE") "0805"))
      (libsource (lib "eagle-import") (part "R0805_IPCR-1.0K-0.1%-0805-0.1W"))
    )
    (comp (ref "R311")
      (value "1.0K")
      (footprint "eagle-import:0805_IPC-7351B")
      (libsource (lib "eagle-import") (part "R0805_IPCR-1.0K-0.1%-0805-0.1W"))
    )
    (comp (ref "R312")
      (value "1.0K")
      (footprint "eagle-import:0805_IPC-7351B")
      (fields (field (name "PACKAGE") "0805"))
      (libsource (lib "eagle-import") (part "R0805_IPCR-1.0K-0.1%-0805-0.1W"))
    )
    (comp (ref "R313")
      (value "1.0K")
      (footprint "eagle-import:0805_IPC-7351B")
      (fields (field (name "PACKAGE") "0805"))
      (libsource (lib "eagle-import") (part "R0805_IPCR-1.0K-0.1%-0805-0.1W"))
    )
    (comp (ref "R314")
      (value "1.0K")
      (footprint "eagle-import:0805_IPC-7351B")
      (libsource (lib "eagle-import") (part "R0805_IPCR-1.0K-0.1%-0805-0.1W"))
    )
    (comp (ref "R315")
      (value "1.0K")
      (footprint "eagle-import:0805_IPC-7351B")
      (fields (field (name "PACKAGE") "0805"))
      (libsource (lib "eagle-import") (part "R0805_IPCR-1.0K-0.1%-0805-0.1W"))
    )
    (comp (ref "R316")
      (value "1.0K")
      (footprint "eagle-import:0805_IPC-7351B")
      (fields (field (name "PACKAGE") "0805"))
      (libsource (lib "eagle-import") (part "R0805_IPCR-1.0K-0.1%-0805-0.1W"))
    )
    (comp (ref "R317")
      (value "1.0K")
      (footprint "eagle-import:0805_IPC-7351B")
      (fields (field (name "PACKAGE") "0805"))
      (libsource (lib "eagle-import") (part "R0805_IPCR-1.0K-0.1%-0805-0.1W"))
    )
    (comp (ref "T301")
      (value "BC808-NPN-SOT23-BEC")
      (footprint "eagle-import:SOT23-BEC")
      (libsource (lib "eagle-import") (part "-NPN-SOT23-BECBC808"))
    )
    (comp (ref "T302")
      (value "BC807-16-PNP-SOT23-BEC")
      (footprint "eagle-import:SOT23-BEC")
      (libsource (lib "eagle-import") (part "-PNP-SOT23-BECBC807-16"))
    )
    (comp (ref "TP11")
      (value "PROBE_TPTP_5MM")
      (footprint "eagle-import:PROBE_TP_5MM")
      (libsource (lib "eagle-import") (part "PROBE_TPTP_5MM"))
    )
    (comp (ref "TP12")
      (value "PROBE_TPTP_5MM")
      (footprint "eagle-import:PROBE_TP_5MM")
      (libsource (lib "eagle-import") (part "PROBE_TPTP_5MM"))
    )
    (comp (ref "TP13")
      (value "PROBE_TPTP_5MM")
      (footprint "eagle-import:PROBE_TP_5MM")
      (libsource (lib "eagle-import") (part "PROBE_TPTP_5MM"))
    )
    (comp (ref "C101")
      (value "0.1uF")
      (footprint "eagle-import:0805_IPC-7351B")
      (fields (field (name "PACKAGE") "0805") (field (name "VOLTAGE") "16V") (field (name "BOM") "INCLUDE"))
      (libsource (lib "eagle-import") (part "C0805_IPCC-0.1U-16V-0805-X7R"))
    )
    (comp (ref "C102")
      (value "0.1uF")
      (footprint "eagle-import:0805_IPC-7351B")
      (fields (field (name "PACKAGE") "0805") (field (name "VOLTAGE") "16V") (field (name "BOM") "INCLUDE"))
      (libsource (lib "eagle-import") (part "C0805_IPCC-0.1U-16V-0805-X7R"))
    )
    (comp (ref "C103")
      (value "0.1uF")
      (footprint "eagle-import:0805_IPC-7351B")
      (fields (field (name "PACKAGE") "0805") (field (name "VOLTAGE") "16V") (field (name "BOM") "INCLUDE"))
      (libsource (lib "eagle-import") (part "C0805_IPCC-0.1U-16V-0805-X7R"))
    )
    (comp (ref "C104")
      (value "0.1uF")
      (footprint "eagle-import:0805_IPC-7351B")
      (fields (field (name "PACKAGE") "0805") (field (name "VOLTAGE") "16V") (field (name "BOM") "INCLUDE"))
      (libsource (lib "eagle-import") (part "C0805_IPCC-0.1U-16V-0805-X7R"))
    )
    (comp (ref "C105")
      (value "0.1uF")
      (footprint "eagle-import:0805_IPC-7351B")
      (fields (field (name "PACKAGE") "0805") (field (name "VOLTAGE") "16V") (field (name "BOM") "INCLUDE"))
      (libsource (lib "eagle-import") (part "C0805_IPCC-0.1U-16V-0805-X7R"))
    )
    (comp (ref "C106")
      (value "0.1uF")
      (footprint "eagle-import:0805_IPC-7351B")
      (fields (field (name "PACKAGE") "0805") (field (name "VOLTAGE") "16V") (field (name "BOM") "INCLUDE"))
      (libsource (lib "eagle-import") (part "C0805_IPCC-0.1U-16V-0805-X7R"))
    )
    (comp (ref "C107")
      (value "0.1uF")
      (footprint "eagle-import:0805_IPC-7351B")
      (fields (field (name "PACKAGE") "0805") (field (name "VOLTAGE") "16V") (field (name "BOM") "INCLUDE"))
      (libsource (lib "eagle-import") (part "C0805_IPCC-0.1U-16V-0805-X7R"))
    )
    (comp (ref "C108")
      (value "0.1uF")
      (footprint "eagle-import:0805_IPC-7351B")
      (fields (field (name "VOLTAGE") "16V"))
      (libsource (lib "eagle-import") (part "C0805_IPCC-0.1U-16V-0805-X7R"))
    )
    (comp (ref "C109")
      (value "0.1uF")
      (footprint "eagle-import:0805_IPC-7351B")
      (fields (field (name "VOLTAGE") "16V"))
      (libsource (lib "eagle-import") (part "C0805_IPCC-0.1U-16V-0805-X7R"))
    )
    (comp (ref "C110")
      (value "0.1uF")
      (footprint "eagle-import:0805_IPC-7351B")
      (fields (field (name "VOLTAGE") "16V"))
      (libsource (lib "eagle-import") (part "C0805_IPCC-0.1U-16V-0805-X7R"))
    )
    (comp (ref "C111")
      (value "0.1uF")
      (footprint "eagle-import:0805_IPC-7351B")
      (fields (field (name "VOLTAGE") "16V"))
      (libsource (lib "eagle-import") (part "C0805_IPCC-0.1U-16V-0805-X7R"))
    )
    (comp (ref "C112")
      (value "22nF")
      (footprint "eagle-import:C1206")
      (fields
        (field (name "BOM") "INCLUDE")
        (field (name "PACKAGE") "1206")
        (field (name "PARTNO") "C3216NP02E223J160AA")
        (field (name "VOLTAGE") "250V")
      )
      (libsource (lib "eagle-import") (part "CC1206C-22N-250V-5%-1206-NP0"))
    )
    (comp (ref "C113")
      (value "22nF")
      (footprint "eagle-import:C1206")
      (fields
        (field (name "BOM") "INCLUDE")
        (field (name "PACKAGE") "1206")
        (field (name "PARTNO") "C3216NP02E223J160AA")
        (field (name "VOLTAGE") "250V")
      )
      (libsource (lib "eagle-import") (part "CC1206C-22N-250V-5%-1206-NP0"))
    )
    (comp (ref "C114")
      (value "0.1uF")
      (footprint "eagle-import:0805_IPC-7351B")
      (fields (field (name "VOLTAGE") "16V"))
      (libsource (lib "eagle-import") (part "C0805_IPCC-0.1U-16V-0805-X7R"))
    )
    (comp (ref "C115")
      (value "0.1uF")
      (footprint "eagle-import:0805_IPC-7351B")
      (fields (field (name "VOLTAGE") "16V"))
      (libsource (lib "eagle-import") (part "C0805_IPCC-0.1U-16V-0805-X7R"))
    )
    (comp (ref "C116")
      (value "0.1uF")
      (footprint "eagle-import:C1812")
      (fields (field (name "VOLTAGE") "16V"))
      (libsource (lib "eagle-import") (part "CC1812"))
    )
    (comp (ref "C117")
      (value "0.1uF")
      (footprint "eagle-import:C1812")
      (fields (field (name "VOLTAGE") "16V"))
      (libsource (lib "eagle-import") (part "CC1812"))
    )
    (comp (ref "C118")
      (value "0.1uF")
      (footprint "eagle-import:C1812")
      (fields (field (name "VOLTAGE") "16V") (field (name "PACKAGE") "1812"))
      (libsource (lib "eagle-import") (part "CC1812"))
    )
    (comp (ref "C119")
      (value "0.1uF")
      (footprint "eagle-import:C1812")
      (fields (field (name "VOLTAGE") "16V") (field (name "PACKAGE") "1812"))
      (libsource (lib "eagle-import") (part "CC1812"))
    )
    (comp (ref "C120")
      (value "0.1uF")
      (footprint "eagle-import:C1812")
      (fields (field (name "VOLTAGE") "16V") (field (name "PACKAGE") "1812"))
      (libsource (lib "eagle-import") (part "CC1812"))
    )
    (comp (ref "J101")
      (value "COAXBNC_EDGE")
      (footprint "eagle-import:BNC_EDGE")
      (libsource (lib "eagle-import") (part "COAXBNC_EDGE"))
    )
    (comp (ref "J102")
      (value "COAXBNC_EDGE")
      (footprint "eagle-import:BNC_EDGE")
      (libsource (lib "eagle-import") (part "COAXBNC_EDGE"))
    )
    (comp (ref "L101")
      (value "1uH")
      (footprint "eagle-import:L1008")
      (fields (field (name "PARTNO") "1008CS-102XJEC"))
      (libsource (lib "eagle-import") (part "L_CHIP1008L-1.0U-AIR-5%-1008-0.37A"))
    )
    (comp (ref "L102")
      (value "1uH")
      (footprint "eagle-import:L1008")
      (fields (field (name "PARTNO") "1008CS-102XJEC"))
      (libsource (lib "eagle-import") (part "L_CHIP1008L-1.0U-AIR-5%-1008-0.37A"))
    )
    (comp (ref "L103")
      (value "L")
      (footprint "eagle-import:DR127")
      (libsource (lib "eagle-import") (part "L"))
    )
    (comp (ref "L104")
      (value "L")
      (footprint "eagle-import:DR127")
      (libsource (lib "eagle-import") (part "L"))
    )
    (comp (ref "Q101")
      (value "IRF520N")
      (footprint "eagle-import:TO220BV")
      (libsource (lib "eagle-import") (part "IRF540"))
    )
    (comp (ref "Q102")
      (value "IRF630")
      (footprint "eagle-import:TO220BV")
      (libsource (lib "eagle-import") (part "IRF540"))
    )
    (comp (ref "R101")
      (value "1.0K")
      (footprint "eagle-import:0805_IPC-7351B")
      (libsource (lib "eagle-import") (part "R0805_IPCR-1.0K-0.1%-0805-0.1W"))
    )
    (comp (ref "R102")
      (value "1K")
      (footprint "eagle-import:R1206")
      (fields (field (name "POWER") "0.25"))
      (libsource (lib "eagle-import") (part "RR1206R-1.0K-1%-1206-0.25W"))
    )
    (comp (ref "R103")
      (value "1K")
      (footprint "eagle-import:R1206")
      (fields (field (name "POWER") "0.25"))
      (libsource (lib "eagle-import") (part "RR1206R-1.0K-1%-1206-0.25W"))
    )
    (comp (ref "R104")
      (value "1K")
      (footprint "eagle-import:R1206")
      (fields (field (name "POWER") "0.25"))
      (libsource (lib "eagle-import") (part "RR1206R-1.0K-1%-1206-0.25W"))
    )
    (comp (ref "R105")
      (value "1K")
      (footprint "eagle-import:R1206")
      (fields (field (name "POWER") "0.25"))
      (libsource (lib "eagle-import") (part "RR1206R-1.0K-1%-1206-0.25W"))
    )
    (comp (ref "R106")
      (value "1K")
      (footprint "eagle-import:R1206")
      (fields (field (name "POWER") "0.25"))
      (libsource (lib "eagle-import") (part "RR1206R-1.0K-1%-1206-0.25W"))
    )
    (comp (ref "R107")
      (value "1K")
      (footprint "eagle-import:R1206")
      (fields (field (name "POWER") "0.25"))
      (libsource (lib "eagle-import") (part "RR1206R-1.0K-1%-1206-0.25W"))
    )
    (comp (ref "R108")
      (value "1.0K")
      (footprint "eagle-import:0805_IPC-7351B")
      (libsource (lib "eagle-import") (part "R0805_IPCR-1.0K-0.1%-0805-0.1W"))
    )
    (comp (ref "R109")
      (value "1K")
      (footprint "eagle-import:R1206")
      (fields (field (name "POWER") "0.25"))
      (libsource (lib "eagle-import") (part "RR1206R-1.0K-1%-1206-0.25W"))
    )
    (comp (ref "R110")
      (value "1.0K")
      (footprint "eagle-import:0805_IPC-7351B")
      (libsource (lib "eagle-import") (part "R0805_IPCR-1.0K-0.1%-0805-0.1W"))
    )
    (comp (ref "R111")
      (value "1K")
      (footprint "eagle-import:R1206")
      (fields (field (name "POWER") "0.25"))
      (libsource (lib "eagle-import") (part "RR1206R-1.0K-1%-1206-0.25W"))
    )
    (comp (ref "R112")
      (value "1.0K")
      (footprint "eagle-import:0805_IPC-7351B")
      (libsource (lib "eagle-import") (part "R0805_IPCR-1.0K-0.1%-0805-0.1W"))
    )
    (comp (ref "R113")
      (value "1.0K")
      (footprint "eagle-import:0805_IPC-7351B")
      (libsource (lib "eagle-import") (part "R0805_IPCR-1.0K-0.1%-0805-0.1W"))
    )
    (comp (ref "R114")
      (value "1.0K")
      (footprint "eagle-import:0805_IPC-7351B")
      (libsource (lib "eagle-import") (part "R0805_IPCR-1.0K-0.1%-0805-0.1W"))
    )
    (comp (ref "R115")
      (value "1.0K")
      (footprint "eagle-import:0805_IPC-7351B")
      (libsource (lib "eagle-import") (part "R0805_IPCR-1.0K-0.1%-0805-0.1W"))
    )
    (comp (ref "R116")
      (value "1.0K")
      (footprint "eagle-import:0805_IPC-7351B")
      (libsource (lib "eagle-import") (part "R0805_IPCR-1.0K-0.1%-0805-0.1W"))
    )
    (comp (ref "R117")
      (value "1.0K")
      (footprint "eagle-import:0805_IPC-7351B")
      (libsource (lib "eagle-import") (part "R0805_IPCR-1.0K-0.1%-0805-0.1W"))
    )
    (comp (ref "R118")
      (value "1K")
      (footprint "eagle-import:R2512")
      (fields (field (name "POWER") "1"))
      (libsource (lib "eagle-import") (part "RR2512R-1K-1%-2512-1W"))
    )
    (comp (ref "R119")
      (value "1K")
      (footprint "eagle-import:R2512")
      (fields (field (name "POWER") "1"))
      (libsource (lib "eagle-import") (part "RR2512R-1K-1%-2512-1W"))
    )
    (comp (ref "R120")
      (value "1K")
      (footprint "eagle-import:R2512")
      (fields (field (name "POWER") "1"))
      (libsource (lib "eagle-import") (part "RR2512R-1K-1%-2512-1W"))
    )
    (comp (ref "R121")
      (value "1K")
      (footprint "eagle-import:R2512")
      (fields (field (name "POWER") "1"))
      (libsource (lib "eagle-import") (part "RR2512R-1K-1%-2512-1W"))
    )
    (comp (ref "R122")
      (value "1K")
      (footprint "eagle-import:R2512")
      (fields (field (name "POWER") "1"))
      (libsource (lib "eagle-import") (part "RR2512R-1K-1%-2512-1W"))
    )
    (comp (ref "R123")
      (value "1K")
      (footprint "eagle-import:R2512")
      (fields (field (name "POWER") "1"))
      (libsource (lib "eagle-import") (part "RR2512R-1K-1%-2512-1W"))
    )
    (comp (ref "R124")
      (value "1K")
      (footprint "eagle-import:R2512")
      (fields (field (name "POWER") "1"))
      (libsource (lib "eagle-import") (part "RR2512R-1K-1%-2512-1W"))
    )
    (comp (ref "R125")
      (value "1K")
      (footprint "eagle-import:R2512")
      (fields (field (name "POWER") "1"))
      (libsource (lib "eagle-import") (part "RR2512R-1K-1%-2512-1W"))
    )
    (comp (ref "R126")
      (value "1K")
      (footprint "eagle-import:R2512")
      (fields (field (name "POWER") "1"))
      (libsource (lib "eagle-import") (part "RR2512R-1K-1%-2512-1W"))
    )
    (comp (ref "R127")
      (value "1K")
      (footprint "eagle-import:R2512")
      (fields (field (name "POWER") "1"))
      (libsource (lib "eagle-import") (part "RR2512R-1K-1%-2512-1W"))
    )
    (comp (ref "R128")
      (value "1K")
      (footprint "eagle-import:R2512")
      (fields (field (name "POWER") "1"))
      (libsource (lib "eagle-import") (part "RR2512R-1K-1%-2512-1W"))
    )
    (comp (ref "R129")
      (value "1K")
      (footprint "eagle-import:R2512")
      (fields (field (name "POWER") "1"))
      (libsource (lib "eagle-import") (part "RR2512R-1K-1%-2512-1W"))
    )
    (comp (ref "R130")
      (value "1.0K")
      (footprint "eagle-import:0805_IPC-7351B")
      (fields (field (name "PACKAGE") "0805"))
      (libsource (lib "eagle-import") (part "R0805_IPCR-1.0K-0.1%-0805-0.1W"))
    )
    (comp (ref "R131")
      (value "1.0K")
      (footprint "eagle-import:0805_IPC-7351B")
      (libsource (lib "eagle-import") (part "R0805_IPCR-1.0K-0.1%-0805-0.1W"))
    )
    (comp (ref "R132")
      (value "1.0K")
      (footprint "eagle-import:0805_IPC-7351B")
      (libsource (lib "eagle-import") (part "R0805_IPCR-1.0K-0.1%-0805-0.1W"))
    )
    (comp (ref "T101")
      (value "HP4_TRAFO")
      (footprint "eagle-import:HP4")
      (libsource (lib "eagle-import") (part "HP4_TRAFO"))
    )
    (comp (ref "T102")
      (value "HP4_TRAFO")
      (footprint "eagle-import:HP4")
      (libsource (lib "eagle-import") (part "HP4_TRAFO"))
    )
    (comp (ref "TP1")
      (value "PROBE_TPTP_5MM")
      (footprint "eagle-import:PROBE_TP_5MM")
      (libsource (lib "eagle-import") (part "PROBE_TPTP_5MM"))
    )
    (comp (ref "TP2")
      (value "PROBE_TPTP_7P5MM")
      (footprint "eagle-import:PROBE_TP_7P5MM")
      (libsource (lib "eagle-import") (part "PROBE_TPTP_7P5MM"))
    )
    (comp (ref "TP3")
      (value "PROBE_TPTP_5MM")
      (footprint "eagle-import:PROBE_TP_5MM")
      (libsource (lib "eagle-import") (part "PROBE_TPTP_5MM"))
    )
    (comp (ref "TP4")
      (value "PROBE_TPTP_7P5MM")
      (footprint "eagle-import:PROBE_TP_7P5MM")
      (libsource (lib "eagle-import") (part "PROBE_TPTP_7P5MM"))
    )
    (comp (ref "TP5")
      (value "PROBE_TPTP_7P5MM")
      (footprint "eagle-import:PROBE_TP_7P5MM")
      (libsource (lib "eagle-import") (part "PROBE_TPTP_7P5MM"))
    )
    (comp (ref "TP6")
      (value "PROBE_TPTP_7P5MM")
      (footprint "eagle-import:PROBE_TP_7P5MM")
      (libsource (lib "eagle-import") (part "PROBE_TPTP_7P5MM"))
    )
    (comp (ref "TP14")
      (value "PROBE_TPTP_5MM")
      (footprint "eagle-import:PROBE_TP_5MM")
      (libsource (lib "eagle-import") (part "PROBE_TPTP_5MM"))
    )
    (comp (ref "TP15")
      (value "PROBE_TPTP_5MM")
      (footprint "eagle-import:PROBE_TP_5MM")
      (libsource (lib "eagle-import") (part "PROBE_TPTP_5MM"))
    )
    (comp (ref "TP18")
      (value "PROBE_TPTP_5MM")
      (footprint "eagle-import:PROBE_TP_5MM")
      (libsource (lib "eagle-import") (part "PROBE_TPTP_5MM"))
    )
    (comp (ref "TP19")
      (value "PROBE_TPTP_5MM")
      (footprint "eagle-import:PROBE_TP_5MM")
      (libsource (lib "eagle-import") (part "PROBE_TPTP_5MM"))
    )
  )
  (nets
    (net (code "1") (name "+5V") (class "Default")
      (node (ref "C306") (pin "1") (pinfunction "1_1") (pintype "passive"))
      (node (ref "C407") (pin "1") (pinfunction "1_1") (pintype "passive"))
      (node (ref "C410") (pin "+") (pinfunction "+_+") (pintype "passive"))
      (node (ref "IC301") (pin "5") (pinfunction "VCC_5") (pintype "power_in"))
      (node (ref "IC402") (pin "OUT") (pinfunction "OUT_OUT") (pintype "passive"))
      (node (ref "LED301") (pin "A") (pinfunction "A_A") (pintype "passive"))
      (node (ref "LED402") (pin "A") (pinfunction "A_A") (pintype "passive"))
      (node (ref "R301") (pin "3") (pinfunction "E_3") (pintype "passive"))
      (node (ref "R408") (pin "1") (pinfunction "1_1") (pintype "passive"))
    )
    (net (code "2") (name "+12V") (class "Default")
      (node (ref "C305") (pin "1") (pinfunction "1_1") (pintype "passive"))
      (node (ref "C406") (pin "1") (pinfunction "1_1") (pintype "passive"))
      (node (ref "C409") (pin "+") (pinfunction "+_+") (pintype "passive"))
      (node (ref "IC302") (pin "4") (pinfunction "V+_4") (pintype "power_in"))
      (node (ref "IC401") (pin "OUT") (pinfunction "OUT_OUT") (pintype "passive"))
      (node (ref "J402") (pin "2") (pinfunction "2_2") (pintype "passive"))
      (node (ref "LED401") (pin "A") (pinfunction "A_A") (pintype "passive"))
      (node (ref "T301") (pin "C") (pinfunction "C_C") (pintype "passive"))
    )
    (net (code "3") (name "ABN1") (class "Default")
      (node (ref "R103") (pin "1") (pinfunction "1_1") (pintype "passive"))
      (node (ref "R105") (pin "1") (pinfunction "1_1") (pintype "passive"))
      (node (ref "R202") (pin "1") (pinfunction "1_1") (pintype "passive"))
      (node (ref "R204") (pin "1") (pinfunction "1_1") (pintype "passive"))
      (node (ref "T101") (pin "11") (pinfunction "F2_11") (pintype "passive"))
      (node (ref "TP18") (pin "TP") (pinfunction "1_TP") (pintype "passive"))
    )
    (net (code "4") (name "ABP1") (class "Default")
      (node (ref "R102") (pin "1") (pinfunction "1_1") (pintype "passive"))
      (node (ref "R104") (pin "1") (pinfunction "1_1") (pintype "passive"))
      (node (ref "R201") (pin "1") (pinfunction "1_1") (pintype "passive"))
      (node (ref "R203") (pin "1") (pinfunction "1_1") (pintype "passive"))
      (node (ref "T101") (pin "1") (pinfunction "S1_1") (pintype "passive"))
      (node (ref "TP19") (pin "TP") (pinfunction "1_TP") (pintype "passive"))
    )
    (net (code "5") (name "AN2") (class "Default")
      (node (ref "C107") (pin "2") (pinfunction "2_2") (pintype "passive"))
      (node (ref "R105") (pin "2") (pinfunction "2_2") (pintype "passive"))
      (node (ref "R107") (pin "1") (pinfunction "1_1") (pintype "passive"))
    )
    (net (code "6") (name "AN3") (class "Default")
      (node (ref "C107") (pin "1") (pinfunction "1_1") (pintype "passive"))
      (node (ref "L102") (pin "1") (pinfunction "1_1") (pintype "passive"))
      (node (ref "R111") (pin "2") (pinfunction "2_2") (pintype "passive"))
      (node (ref "R113") (pin "1") (pinfunction "1_1") (pintype "passive"))
      (node (ref "R115") (pin "1") (pinfunction "1_1") (pintype "passive"))
    )
    (net (code "7") (name "AN4") (class "Default")
      (node (ref "L102") (pin "2") (pinfunction "2_2") (pintype "passive"))
      (node (ref "Q102") (pin "G") (pinfunction "G_G") (pintype "passive"))
      (node (ref "R115") (pin "2") (pinfunction "2_2") (pintype "passive"))
      (node (ref "R117") (pin "1") (pinfunction "1_1") (pintype "passive"))
      (node (ref "R120") (pin "1") (pinfunction "1_1") (pintype "passive"))
      (node (ref "R121") (pin "1") (pinfunction "1_1") (pintype "passive"))
      (node (ref "TP3") (pin "TP") (pinfunction "1_TP") (pintype "passive"))
    )
    (net (code "8") (name "AN5") (class "Default")
      (node (ref "Q102") (pin "S") (pinfunction "S_S") (pintype "passive"))
      (node (ref "R123") (pin "1") (pinfunction "1_1") (pintype "passive"))
      (node (ref "R125") (pin "1") (pinfunction "1_1") (pintype "passive"))
      (node (ref "R127") (pin "1") (pinfunction "1_1") (pintype "passive"))
      (node (ref "R129") (pin "1") (pinfunction "1_1") (pintype "passive"))
      (node (ref "R131") (pin "1") (pinfunction "1_1") (pintype "passive"))
      (node (ref "TP6") (pin "TP") (pinfunction "1_TP") (pintype "passive"))
    )
    (net (code "9") (name "AN6") (class "Default")
      (node (ref "C115") (pin "1") (pinfunction "1_1") (pintype "passive"))
      (node (ref "R131") (pin "2") (pinfunction "2_2") (pintype "passive"))
      (node (ref "TP15") (pin "TP") (pinfunction "1_TP") (pintype "passive"))
    )
    (net (code "10") (name "AP2") (class "Default")
      (node (ref "C105") (pin "2") (pinfunction "2_2") (pintype "passive"))
      (node (ref "R104") (pin "2") (pinfunction "2_2") (pintype "passive"))
      (node (ref "R106") (pin "1") (pinfunction "1_1") (pintype "passive"))
    )
    (net (code "11") (name "AP3") (class "Default")
      (node (ref "C105") (pin "1") (pinfunction "1_1") (pintype "passive"))
      (node (ref "L101") (pin "1") (pinfunction "1_1") (pintype "passive"))
      (node (ref "R109") (pin "2") (pinfunction "2_2") (pintype "passive"))
      (node (ref "R112") (pin "1") (pinfunction "1_1") (pintype "passive"))
      (node (ref "R114") (pin "1") (pinfunction "1_1") (pintype "passive"))
    )
    (net (code "12") (name "AP4") (class "Default")
      (node (ref "L101") (pin "2") (pinfunction "2_2") (pintype "passive"))
      (node (ref "Q101") (pin "G") (pinfunction "G_G") (pintype "passive"))
      (node (ref "R114") (pin "2") (pinfunction "2_2") (pintype "passive"))
      (node (ref "R116") (pin "1") (pinfunction "1_1") (pintype "passive"))
      (node (ref "R118") (pin "1") (pinfunction "1_1") (pintype "passive"))
      (node (ref "R119") (pin "1") (pinfunction "1_1") (pintype "passive"))
      (node (ref "TP1") (pin "TP") (pinfunction "1_TP") (pintype "passive"))
    )
    (net (code "13") (name "AP5") (class "Default")
      (node (ref "Q101") (pin "S") (pinfunction "S_S") (pintype "passive"))
      (node (ref "R122") (pin "1") (pinfunction "1_1") (pintype "passive"))
      (node (ref "R124") (pin "1") (pinfunction "1_1") (pintype "passive"))
      (node (ref "R126") (pin "1") (pinfunction "1_1") (pintype "passive"))
      (node (ref "R128") (pin "1") (pinfunction "1_1") (pintype "passive"))
      (node (ref "R130") (pin "1") (pinfunction "1_1") (pintype "passive"))
      (node (ref "TP5") (pin "TP") (pinfunction "1_TP") (pintype "passive"))
    )
    (net (code "14") (name "AP6") (class "Default")
      (node (ref "C114") (pin "1") (pinfunction "1_1") (pintype "passive"))
      (node (ref "R130") (pin "2") (pinfunction "2_2") (pintype "passive"))
      (node (ref "TP14") (pin "TP") (pinfunction "1_TP") (pintype "passive"))
    )
    (net (code "15") (name "BN2") (class "Default")
      (node (ref "C204") (pin "2") (pinfunction "2_2") (pintype "passive"))
      (node (ref "R204") (pin "2") (pinfunction "2_2") (pintype "passive"))
      (node (ref "R206") (pin "1") (pinfunction "1_1") (pintype "passive"))
    )
    (net (code "16") (name "BN3") (class "Default")
      (node (ref "C204") (pin "1") (pinfunction "1_1") (pintype "passive"))
      (node (ref "L202") (pin "1") (pinfunction "1_1") (pintype "passive"))
      (node (ref "R210") (pin "2") (pinfunction "2_2") (pintype "passive"))
      (node (ref "R212") (pin "1") (pinfunction "1_1") (pintype "passive"))
      (node (ref "R214") (pin "1") (pinfunction "1_1") (pintype "passive"))
    )
    (net (code "17") (name "BN4") (class "Default")
      (node (ref "L202") (pin "2") (pinfunction "2_2") (pintype "passive"))
      (node (ref "Q202") (pin "G") (pinfunction "G_G") (pintype "passive"))
      (node (ref "R214") (pin "2") (pinfunction "2_2") (pintype "passive"))
      (node (ref "R216") (pin "1") (pinfunction "1_1") (pintype "passive"))
      (node (ref "R219") (pin "1") (pinfunction "1_1") (pintype "passive"))
      (node (ref "R220") (pin "1") (pinfunction "1_1") (pintype "passive"))
      (node (ref "TP9") (pin "TP") (pinfunction "1_TP") (pintype "passive"))
    )
    (net (code "18") (name "BN5") (class "Default")
      (node (ref "Q202") (pin "S") (pinfunction "S_S") (pintype "passive"))
      (node (ref "R222") (pin "1") (pinfunction "1_1") (pintype "passive"))
      (node (ref "R224") (pin "1") (pinfunction "1_1") (pintype "passive"))
      (node (ref "R226") (pin "1") (pinfunction "1_1") (pintype "passive"))
      (node (ref "R228") (pin "1") (pinfunction "1_1") (pintype "passive"))
      (node (ref "R230") (pin "1") (pinfunction "1_1") (pintype "passive"))
      (node (ref "TP10") (pin "TP") (pinfunction "1_TP") (pintype "passive"))
    )
    (net (code "19") (name "BN6") (class "Default")
      (node (ref "C212") (pin "1") (pinfunction "1_1") (pintype "passive"))
      (node (ref "R230") (pin "2") (pinfunction "2_2") (pintype "passive"))
      (node (ref "TP17") (pin "TP") (pinfunction "1_TP") (pintype "passive"))
    )
    (net (code "20") (name "BP2") (class "Default")
      (node (ref "C202") (pin "2") (pinfunction "2_2") (pintype "passive"))
      (node (ref "R203") (pin "2") (pinfunction "2_2") (pintype "passive"))
      (node (ref "R205") (pin "1") (pinfunction "1_1") (pintype "passive"))
    )
    (net (code "21") (name "BP3") (class "Default")
      (node (ref "C202") (pin "1") (pinfunction "1_1") (pintype "passive"))
      (node (ref "L201") (pin "1") (pinfunction "1_1") (pintype "passive"))
      (node (ref "R208") (pin "2") (pinfunction "2_2") (pintype "passive"))
      (node (ref "R211") (pin "1") (pinfunction "1_1") (pintype "passive"))
      (node (ref "R213") (pin "1") (pinfunction "1_1") (pintype "passive"))
    )
    (net (code "22") (name "BP4") (class "Default")
      (node (ref "L201") (pin "2") (pinfunction "2_2") (pintype "passive"))
      (node (ref "Q201") (pin "G") (pinfunction "G_G") (pintype "passive"))
      (node (ref "R213") (pin "2") (pinfunction "2_2") (pintype "passive"))
      (node (ref "R215") (pin "1") (pinfunction "1_1") (pintype "passive"))
      (node (ref "R217") (pin "1") (pinfunction "1_1") (pintype "passive"))
      (node (ref "R218") (pin "1") (pinfunction "1_1") (pintype "passive"))
      (node (ref "TP7") (pin "TP") (pinfunction "1_TP") (pintype "passive"))
    )
    (net (code "23") (name "BP5") (class "Default")
      (node (ref "Q201") (pin "S") (pinfunction "S_S") (pintype "passive"))
      (node (ref "R221") (pin "1") (pinfunction "1_1") (pintype "passive"))
      (node (ref "R223") (pin "1") (pinfunction "1_1") (pintype "passive"))
      (node (ref "R225") (pin "1") (pinfunction "1_1") (pintype "passive"))
      (node (ref "R227") (pin "1") (pinfunction "1_1") (pintype "passive"))
      (node (ref "R229") (pin "1") (pinfunction "1_1") (pintype "passive"))
      (node (ref "TP8") (pin "TP") (pinfunction "1_TP") (pintype "passive"))
    )
    (net (code "24") (name "BP6") (class "Default")
      (node (ref "C211") (pin "1") (pinfunction "1_1") (pintype "passive"))
      (node (ref "R229") (pin "2") (pinfunction "2_2") (pintype "passive"))
      (node (ref "TP16") (pin "TP") (pinfunction "1_TP") (pintype "passive"))
    )
    (net (code "25") (name "DRAINS_NEG") (class "Default")
      (node (ref "C113") (pin "2") (pinfunction "2_2") (pintype "passive"))
      (node (ref "C117") (pin "2") (pinfunction "2_2") (pintype "passive"))
      (node (ref "C210") (pin "2") (pinfunction "2_2") (pintype "passive"))
      (node (ref "L104") (pin "1") (pinfunction "1_1") (pintype "passive"))
      (node (ref "Q102") (pin "D") (pinfunction "D_D") (pintype "passive"))
      (node (ref "Q202") (pin "D") (pinfunction "D_D") (pintype "passive"))
      (node (ref "T102") (pin "8") (pinfunction "F5_8") (pintype "passive"))
      (node (ref "TP4") (pin "TP") (pinfunction "1_TP") (pintype "passive"))
    )
    (net (code "26") (name "DRAINS_POS") (class "Default")
      (node (ref "C112") (pin "2") (pinfunction "2_2") (pintype "passive"))
      (node (ref "C116") (pin "2") (pinfunction "2_2") (pintype "passive"))
      (node (ref "C209") (pin "2") (pinfunction "2_2") (pintype "passive"))
      (node (ref "L103") (pin "1") (pinfunction "1_1") (pintype "passive"))
      (node (ref "Q101") (pin "D") (pinfunction "D_D") (pintype "passive"))
      (node (ref "Q201") (pin "D") (pinfunction "D_D") (pintype "passive"))
      (node (ref "T102") (pin "6") (pinfunction "S6_6") (pintype "passive"))
      (node (ref "TP2") (pin "TP") (pinfunction "1_TP") (pintype "passive"))
    )
    (net (code "27") (name "GBIAS") (class "Default")
      (node (ref "R108") (pin "1") (pinfunction "1_1") (pintype "passive"))
      (node (ref "R110") (pin "1") (pinfunction "1_1") (pintype "passive"))
      (node (ref "R207") (pin "1") (pinfunction "1_1") (pintype "passive"))
      (node (ref "R209") (pin "1") (pinfunction "1_1") (pintype "passive"))
      (node (ref "R316") (pin "2") (pinfunction "2_2") (pintype "passive"))
      (node (ref "R317") (pin "2") (pinfunction "2_2") (pintype "passive"))
      (node (ref "T301") (pin "E") (pinfunction "E_E") (pintype "passive"))
      (node (ref "T302") (pin "E") (pinfunction "E_E") (pintype "passive"))
      (node (ref "TP11") (pin "TP") (pinfunction "1_TP") (pintype "passive"))
    )
    (net (code "28") (name "GND") (class "Default")
      (node (ref "C104") (pin "2") (pinfunction "2_2") (pintype "passive"))
      (node (ref "C106") (pin "2") (pinfunction "2_2") (pintype "passive"))
      (node (ref "C108") (pin "2") (pinfunction "2_2") (pintype "passive"))
      (node (ref "C109") (pin "2") (pinfunction "2_2") (pintype "passive"))
      (node (ref "C110") (pin "2") (pinfunction "2_2") (pintype "passive"))
      (node (ref "C111") (pin "2") (pinfunction "2_2") (pintype "passive"))
      (node (ref "C114") (pin "2") (pinfunction "2_2") (pintype "passive"))
      (node (ref "C115") (pin "2") (pinfunction "2_2") (pintype "passive"))
      (node (ref "C201") (pin "2") (pinfunction "2_2") (pintype "passive"))
      (node (ref "C203") (pin "2") (pinfunction "2_2") (pintype "passive"))
      (node (ref "C205") (pin "2") (pinfunction "2_2") (pintype "passive"))
      (node (ref "C206") (pin "2") (pinfunction "2_2") (pintype "passive"))
      (node (ref "C207") (pin "2") (pinfunction "2_2") (pintype "passive"))
      (node (ref "C208") (pin "2") (pinfunction "2_2") (pintype "passive"))
      (node (ref "C211") (pin "2") (pinfunction "2_2") (pintype "passive"))
      (node (ref "C212") (pin "2") (pinfunction "2_2") (pintype "passive"))
      (node (ref "C301") (pin "2") (pinfunction "2_2") (pintype "passive"))
      (node (ref "C302") (pin "2") (pinfunction "2_2") (pintype "passive"))
      (node (ref "C303") (pin "2") (pinfunction "2_2") (pintype "passive"))
      (node (ref "C305") (pin "2") (pinfunction "2_2") (pintype "passive"))
      (node (ref "C306") (pin "2") (pinfunction "2_2") (pintype "passive"))
      (node (ref "C401") (pin "-") (pinfunction "-_-") (pintype "passive"))
      (node (ref "C402") (pin "2") (pinfunction "2_2") (pintype "passive"))
      (node (ref "C403") (pin "2") (pinfunction "2_2") (pintype "passive"))
      (node (ref "C404") (pin "2") (pinfunction "2_2") (pintype "passive"))
      (node (ref "C405") (pin "2") (pinfunction "2_2") (pintype "passive"))
      (node (ref "C406") (pin "2") (pinfunction "2_2") (pintype "passive"))
      (node (ref "C407") (pin "2") (pinfunction "2_2") (pintype "passive"))
      (node (ref "C408") (pin "2") (pinfunction "2_2") (pintype "passive"))
      (node (ref "C409") (pin "-") (pinfunction "-_-") (pintype "passive"))
      (node (ref "C410") (pin "-") (pinfunction "-_-") (pintype "passive"))
      (node (ref "C411") (pin "2") (pinfunction "2_2") (pintype "passive"))
      (node (ref "C412") (pin "2") (pinfunction "2_2") (pintype "passive"))
      (node (ref "C413") (pin "2") (pinfunction "2_2") (pintype "passive"))
      (node (ref "D401") (pin "A") (pinfunction "A1_A") (pintype "passive"))
      (node (ref "H401") (pin "B3,2") (pinfunction "MOUNT_B3,2") (pintype "passive"))
      (node (ref "H402") (pin "B3,2") (pinfunction "MOUNT_B3,2") (pintype "passive"))
      (node (ref "H403") (pin "B3,2") (pinfunction "MOUNT_B3,2") (pintype "passive"))
      (node (ref "H404") (pin "B3,2") (pinfunction "MOUNT_B3,2") (pintype "passive"))
      (node (ref "IC301") (pin "3") (pinfunction "GND_3") (pintype "power_in"))
      (node (ref "IC302") (pin "11") (pinfunction "V-_11") (pintype "power_in"))
      (node (ref "IC401") (pin "GND") (pinfunction "GND_GND") (pintype "input"))
      (node (ref "IC402") (pin "GND") (pinfunction "GND_GND") (pintype "input"))
      (node (ref "J101") (pin "G1") (pinfunction "GND1_G1") (pintype "power_in"))
      (node (ref "J101") (pin "G2") (pinfunction "GND1_G2") (pintype "power_in"))
      (node (ref "J101") (pin "G3") (pinfunction "GND1_G3") (pintype "power_in"))
      (node (ref "J101") (pin "G4") (pinfunction "GND1_G4") (pintype "power_in"))
      (node (ref "J102") (pin "G1") (pinfunction "GND1_G1") (pintype "power_in"))
      (node (ref "J102") (pin "G2") (pinfunction "GND1_G2") (pintype "power_in"))
      (node (ref "J102") (pin "G3") (pinfunction "GND1_G3") (pintype "power_in"))
      (node (ref "J102") (pin "G4") (pinfunction "GND1_G4") (pintype "power_in"))
      (node (ref "J302") (pin "G1") (pinfunction "GND1_G1") (pintype "power_in"))
      (node (ref "J302") (pin "G2") (pinfunction "GND1_G2") (pintype "power_in"))
      (node (ref "J302") (pin "G3") (pinfunction "GND1_G3") (pintype "power_in"))
      (node (ref "J302") (pin "G4") (pinfunction "GND1_G4") (pintype "power_in"))
      (node (ref "J402") (pin "1") (pinfunction "1_1") (pintype "passive"))
      (node (ref "Q301") (pin "2") (pinfunction "S_2") (pintype "passive"))
      (node (ref "R101") (pin "2") (pinfunction "2_2") (pintype "passive"))
      (node (ref "R102") (pin "2") (pinfunction "2_2") (pintype "passive"))
      (node (ref "R103") (pin "2") (pinfunction "2_2") (pintype "passive"))
      (node (ref "R106") (pin "2") (pinfunction "2_2") (pintype "passive"))
      (node (ref "R107") (pin "2") (pinfunction "2_2") (pintype "passive"))
      (node (ref "R122") (pin "2") (pinfunction "2_2") (pintype "passive"))
      (node (ref "R123") (pin "2") (pinfunction "2_2") (pintype "passive"))
      (node (ref "R124") (pin "2") (pinfunction "2_2") (pintype "passive"))
      (node (ref "R125") (pin "2") (pinfunction "2_2") (pintype "passive"))
      (node (ref "R126") (pin "2") (pinfunction "2_2") (pintype "passive"))
      (node (ref "R127") (pin "2") (pinfunction "2_2") (pintype "passive"))
      (node (ref "R128") (pin "2") (pinfunction "2_2") (pintype "passive"))
      (node (ref "R129") (pin "2") (pinfunction "2_2") (pintype "passive"))
      (node (ref "R201") (pin "2") (pinfunction "2_2") (pintype "passive"))
      (node (ref "R202") (pin "2") (pinfunction "2_2") (pintype "passive"))
      (node (ref "R205") (pin "2") (pinfunction "2_2") (pintype "passive"))
      (node (ref "R206") (pin "2") (pinfunction "2_2") (pintype "passive"))
      (node (ref "R221") (pin "2") (pinfunction "2_2") (pintype "passive"))
      (node (ref "R222") (pin "2") (pinfunction "2_2") (pintype "passive"))
      (node (ref "R223") (pin "2") (pinfunction "2_2") (pintype "passive"))
      (node (ref "R224") (pin "2") (pinfunction "2_2") (pintype "passive"))
      (node (ref "R225") (pin "2") (pinfunction "2_2") (pintype "passive"))
      (node (ref "R226") (pin "2") (pinfunction "2_2") (pintype "passive"))
      (node (ref "R227") (pin "2") (pinfunction "2_2") (pintype "passive"))
      (node (ref "R228") (pin "2") (pinfunction "2_2") (pintype "passive"))
      (node (ref "R301") (pin "1") (pinfunction "A_1") (pintype "passive"))
      (node (ref "R307") (pin "2") (pinfunction "2_2") (pintype "passive"))
      (node (ref "R311") (pin "2") (pinfunction "2_2") (pintype "passive"))
      (node (ref "R312") (pin "1") (pinfunction "1_1") (pintype "passive"))
      (node (ref "R406") (pin "2") (pinfunction "2_2") (pintype "passive"))
      (node (ref "R407") (pin "2") (pinfunction "2_2") (pintype "passive"))
      (node (ref "T101") (pin "10") (pinfunction "F3_10") (pintype "passive"))
      (node (ref "T102") (pin "9") (pinfunction "F4_9") (pintype "passive"))
      (node (ref "T302") (pin "C") (pinfunction "C_C") (pintype "passive"))
      (node (ref "TP1") (pin "GND") (pinfunction "GND1_GND") (pintype "power_in"))
      (node (ref "TP10") (pin "GND") (pinfunction "GND1_GND") (pintype "power_in"))
      (node (ref "TP11") (pin "GND") (pinfunction "GND1_GND") (pintype "power_in"))
      (node (ref "TP12") (pin "GND") (pinfunction "GND1_GND") (pintype "power_in"))
      (node (ref "TP13") (pin "GND") (pinfunction "GND1_GND") (pintype "power_in"))
      (node (ref "TP14") (pin "GND") (pinfunction "GND1_GND") (pintype "power_in"))
      (node (ref "TP15") (pin "GND") (pinfunction "GND1_GND") (pintype "power_in"))
      (node (ref "TP16") (pin "GND") (pinfunction "GND1_GND") (pintype "power_in"))
      (node (ref "TP17") (pin "GND") (pinfunction "GND1_GND") (pintype "power_in"))
      (node (ref "TP18") (pin "GND") (pinfunction "GND1_GND") (pintype "power_in"))
      (node (ref "TP19") (pin "GND") (pinfunction "GND1_GND") (pintype "power_in"))
      (node (ref "TP2") (pin "GND") (pinfunction "GND1_GND") (pintype "power_in"))
      (node (ref "TP3") (pin "GND") (pinfunction "GND1_GND") (pintype "power_in"))
      (node (ref "TP4") (pin "GND") (pinfunction "GND1_GND") (pintype "power_in"))
      (node (ref "TP5") (pin "GND") (pinfunction "GND1_GND") (pintype "power_in"))
      (node (ref "TP6") (pin "GND") (pinfunction "GND1_GND") (pintype "power_in"))
      (node (ref "TP7") (pin "GND") (pinfunction "GND1_GND") (pintype "power_in"))
      (node (ref "TP8") (pin "GND") (pinfunction "GND1_GND") (pintype "power_in"))
      (node (ref "TP9") (pin "GND") (pinfunction "GND1_GND") (pintype "power_in"))
      (node (ref "X401") (pin "2") (pinfunction "KL_2") (pintype "passive"))
      (node (ref "X402") (pin "P1") (pinfunction "P$1_P1") (pintype "bidirectional"))
      (node (ref "X402") (pin "P2") (pinfunction "P$2_P2") (pintype "bidirectional"))
    )
    (net (code "29") (name "Net-(C104-Pad1)") (class "Default")
      (node (ref "C104") (pin "1") (pinfunction "1_1") (pintype "passive"))
      (node (ref "R108") (pin "2") (pinfunction "2_2") (pintype "passive"))
      (node (ref "R109") (pin "1") (pinfunction "1_1") (pintype "passive"))
    )
    (net (code "30") (name "Net-(C106-Pad1)") (class "Default")
      (node (ref "C106") (pin "1") (pinfunction "1_1") (pintype "passive"))
      (node (ref "R110") (pin "2") (pinfunction "2_2") (pintype "passive"))
      (node (ref "R111") (pin "1") (pinfunction "1_1") (pintype "passive"))
    )
    (net (code "31") (name "Net-(C108-Pad1)") (class "Default")
      (node (ref "C108") (pin "1") (pinfunction "1_1") (pintype "passive"))
      (node (ref "R112") (pin "2") (pinfunction "2_2") (pintype "passive"))
    )
    (net (code "32") (name "Net-(C109-Pad1)") (class "Default")
      (node (ref "C109") (pin "1") (pinfunction "1_1") (pintype "passive"))
      (node (ref "R113") (pin "2") (pinfunction "2_2") (pintype "passive"))
    )
    (net (code "33") (name "Net-(C110-Pad1)") (class "Default")
      (node (ref "C110") (pin "1") (pinfunction "1_1") (pintype "passive"))
      (node (ref "R116") (pin "2") (pinfunction "2_2") (pintype "passive"))
    )
    (net (code "34") (name "Net-(C111-Pad1)") (class "Default")
      (node (ref "C111") (pin "1") (pinfunction "1_1") (pintype "passive"))
      (node (ref "R117") (pin "2") (pinfunction "2_2") (pintype "passive"))
    )
    (net (code "35") (name "Net-(C112-Pad1)") (class "Default")
      (node (ref "C112") (pin "1") (pinfunction "1_1") (pintype "passive"))
      (node (ref "R118") (pin "2") (pinfunction "2_2") (pintype "passive"))
      (node (ref "R119") (pin "2") (pinfunction "2_2") (pintype "passive"))
    )
    (net (code "36") (name "Net-(C113-Pad1)") (class "Default")
      (node (ref "C113") (pin "1") (pinfunction "1_1") (pintype "passive"))
      (node (ref "R120") (pin "2") (pinfunction "2_2") (pintype "passive"))
      (node (ref "R121") (pin "2") (pinfunction "2_2") (pintype "passive"))
    )
    (net (code "37") (name "Net-(C201-Pad1)") (class "Default")
      (node (ref "C201") (pin "1") (pinfunction "1_1") (pintype "passive"))
      (node (ref "R207") (pin "2") (pinfunction "2_2") (pintype "passive"))
      (node (ref "R208") (pin "1") (pinfunction "1_1") (pintype "passive"))
    )
    (net (code "38") (name "Net-(C203-Pad1)") (class "Default")
      (node (ref "C203") (pin "1") (pinfunction "1_1") (pintype "passive"))
      (node (ref "R209") (pin "2") (pinfunction "2_2") (pintype "passive"))
      (node (ref "R210") (pin "1") (pinfunction "1_1") (pintype "passive"))
    )
    (net (code "39") (name "Net-(C205-Pad1)") (class "Default")
      (node (ref "C205") (pin "1") (pinfunction "1_1") (pintype "passive"))
      (node (ref "R211") (pin "2") (pinfunction "2_2") (pintype "passive"))
    )
    (net (code "40") (name "Net-(C206-Pad1)") (class "Default")
      (node (ref "C206") (pin "1") (pinfunction "1_1") (pintype "passive"))
      (node (ref "R212") (pin "2") (pinfunction "2_2") (pintype "passive"))
    )
    (net (code "41") (name "Net-(C207-Pad1)") (class "Default")
      (node (ref "C207") (pin "1") (pinfunction "1_1") (pintype "passive"))
      (node (ref "R215") (pin "2") (pinfunction "2_2") (pintype "passive"))
    )
    (net (code "42") (name "Net-(C208-Pad1)") (class "Default")
      (node (ref "C208") (pin "1") (pinfunction "1_1") (pintype "passive"))
      (node (ref "R216") (pin "2") (pinfunction "2_2") (pintype "passive"))
    )
    (net (code "43") (name "Net-(C209-Pad1)") (class "Default")
      (node (ref "C209") (pin "1") (pinfunction "1_1") (pintype "passive"))
      (node (ref "R217") (pin "2") (pinfunction "2_2") (pintype "passive"))
      (node (ref "R218") (pin "2") (pinfunction "2_2") (pintype "passive"))
    )
    (net (code "44") (name "Net-(C210-Pad1)") (class "Default")
      (node (ref "C210") (pin "1") (pinfunction "1_1") (pintype "passive"))
      (node (ref "R219") (pin "2") (pinfunction "2_2") (pintype "passive"))
      (node (ref "R220") (pin "2") (pinfunction "2_2") (pintype "passive"))
    )
    (net (code "45") (name "Net-(C302-Pad1)") (class "Default")
      (node (ref "C302") (pin "1") (pinfunction "1_1") (pintype "passive"))
      (node (ref "R313") (pin "1") (pinfunction "1_1") (pintype "passive"))
    )
    (net (code "46") (name "Net-(C304-Pad1)") (class "Default")
      (node (ref "C304") (pin "1") (pinfunction "1_1") (pintype "passive"))
      (node (ref "R314") (pin "2") (pinfunction "2_2") (pintype "passive"))
    )
    (net (code "47") (name "Net-(C403-Pad1)") (class "Default")
      (node (ref "C403") (pin "1") (pinfunction "1_1") (pintype "passive"))
      (node (ref "IC401") (pin "IN") (pinfunction "IN_IN") (pintype "input"))
      (node (ref "R402") (pin "2") (pinfunction "2_2") (pintype "passive"))
    )
    (net (code "48") (name "Net-(C404-Pad1)") (class "Default")
      (node (ref "C404") (pin "1") (pinfunction "1_1") (pintype "passive"))
      (node (ref "IC402") (pin "IN") (pinfunction "IN_IN") (pintype "input"))
      (node (ref "R403") (pin "2") (pinfunction "2_2") (pintype "passive"))
    )
    (net (code "49") (name "Net-(C405-Pad1)") (class "Default")
      (node (ref "C405") (pin "1") (pinfunction "1_1") (pintype "passive"))
      (node (ref "L401") (pin "2") (pinfunction "2_2") (pintype "passive"))
      (node (ref "L402") (pin "1") (pinfunction "1_1") (pintype "passive"))
      (node (ref "R404") (pin "1") (pinfunction "1_1") (pintype "passive"))
      (node (ref "R405") (pin "1") (pinfunction "1_1") (pintype "passive"))
    )
    (net (code "50") (name "Net-(D401-C1)") (class "Default")
      (node (ref "D401") (pin "K") (pinfunction "C1_K") (pintype "passive"))
      (node (ref "J401") (pin "2") (pinfunction "2_2") (pintype "passive"))
      (node (ref "R401") (pin "1") (pinfunction "1_1") (pintype "passive"))
    )
    (net (code "51") (name "Net-(D402-A1)") (class "Default")
      (node (ref "D402") (pin "A") (pinfunction "A1_A") (pintype "passive"))
      (node (ref "R402") (pin "1") (pinfunction "1_1") (pintype "passive"))
      (node (ref "R403") (pin "1") (pinfunction "1_1") (pintype "passive"))
    )
    (net (code "52") (name "Net-(D402-C1)") (class "Default")
      (node (ref "C401") (pin "+") (pinfunction "+_+") (pintype "passive"))
      (node (ref "C402") (pin "1") (pinfunction "1_1") (pintype "passive"))
      (node (ref "D402") (pin "C") (pinfunction "C1_C") (pintype "passive"))
      (node (ref "L401") (pin "1") (pinfunction "1_1") (pintype "passive"))
      (node (ref "R401") (pin "2") (pinfunction "2_2") (pintype "passive"))
    )
    (net (code "53") (name "Net-(IC301A-I)") (class "Default")
      (node (ref "IC301") (pin "2") (pinfunction "I_2") (pintype "input"))
      (node (ref "R304") (pin "2") (pinfunction "2_2") (pintype "passive"))
      (node (ref "R307") (pin "1") (pinfunction "1_1") (pintype "passive"))
    )
    (net (code "54") (name "Net-(IC301A-O)") (class "Default")
      (node (ref "IC301") (pin "4") (pinfunction "O_4") (pintype "output"))
      (node (ref "Q301") (pin "1") (pinfunction "G_1") (pintype "passive"))
      (node (ref "R309") (pin "2") (pinfunction "2_2") (pintype "passive"))
    )
    (net (code "55") (name "Net-(IC302A-+IN)") (class "Default")
      (node (ref "C303") (pin "1") (pinfunction "1_1") (pintype "passive"))
      (node (ref "IC302") (pin "3") (pinfunction "+IN_3") (pintype "input"))
      (node (ref "R310") (pin "2") (pinfunction "2_2") (pintype "passive"))
      (node (ref "R311") (pin "1") (pinfunction "1_1") (pintype "passive"))
    )
    (net (code "56") (name "Net-(IC302A--IN)") (class "Default")
      (node (ref "C304") (pin "2") (pinfunction "2_2") (pintype "passive"))
      (node (ref "IC302") (pin "2") (pinfunction "-IN_2") (pintype "input"))
      (node (ref "R312") (pin "2") (pinfunction "2_2") (pintype "passive"))
      (node (ref "R313") (pin "2") (pinfunction "2_2") (pintype "passive"))
      (node (ref "R317") (pin "1") (pinfunction "1_1") (pintype "passive"))
    )
    (net (code "57") (name "Net-(IC302A-OUT)") (class "Default")
      (node (ref "IC302") (pin "1") (pinfunction "OUT_1") (pintype "output"))
      (node (ref "R314") (pin "1") (pinfunction "1_1") (pintype "passive"))
      (node (ref "R315") (pin "1") (pinfunction "1_1") (pintype "passive"))
    )
    (net (code "58") (name "Net-(IC302B-+IN)") (class "Default")
      (node (ref "IC302") (pin "5") (pinfunction "+IN_5") (pintype "input"))
      (node (ref "Q301") (pin "3") (pinfunction "D_3") (pintype "passive"))
      (node (ref "R308") (pin "2") (pinfunction "2_2") (pintype "passive"))
    )
    (net (code "59") (name "Net-(IC302B--IN)") (class "Default")
      (node (ref "IC302") (pin "6") (pinfunction "-IN_6") (pintype "input"))
      (node (ref "IC302") (pin "7") (pinfunction "OUT_7") (pintype "output"))
      (node (ref "R310") (pin "1") (pinfunction "1_1") (pintype "passive"))
      (node (ref "TP12") (pin "TP") (pinfunction "1_TP") (pintype "passive"))
    )
    (net (code "60") (name "Net-(IC302C-+IN)") (class "Default")
      (node (ref "IC302") (pin "10") (pinfunction "+IN_10") (pintype "input"))
      (node (ref "R303") (pin "2") (pinfunction "2_2") (pintype "passive"))
      (node (ref "R306") (pin "1") (pinfunction "1_1") (pintype "passive"))
    )
    (net (code "61") (name "Net-(IC302C--IN)") (class "Default")
      (node (ref "IC302") (pin "9") (pinfunction "-IN_9") (pintype "input"))
      (node (ref "JP302") (pin "1") (pinfunction "1_1") (pintype "passive"))
      (node (ref "R302") (pin "2") (pinfunction "2_2") (pintype "passive"))
      (node (ref "R305") (pin "1") (pinfunction "1_1") (pintype "passive"))
    )
    (net (code "62") (name "Net-(IC302C-OUT)") (class "Default")
      (node (ref "IC302") (pin "8") (pinfunction "OUT_8") (pintype "output"))
      (node (ref "JP302") (pin "2") (pinfunction "2_2") (pintype "passive"))
      (node (ref "R305") (pin "2") (pinfunction "2_2") (pintype "passive"))
      (node (ref "R308") (pin "1") (pinfunction "1_1") (pintype "passive"))
    )
    (net (code "63") (name "Net-(IC302D-+IN)") (class "Default")
      (node (ref "C301") (pin "1") (pinfunction "1_1") (pintype "passive"))
      (node (ref "IC302") (pin "12") (pinfunction "+IN_12") (pintype "input"))
      (node (ref "R301") (pin "2") (pinfunction "S_2") (pintype "passive"))
    )
    (net (code "64") (name "Net-(IC302D--IN)") (class "Default")
      (node (ref "IC302") (pin "13") (pinfunction "-IN_13") (pintype "input"))
      (node (ref "IC302") (pin "14") (pinfunction "OUT_14") (pintype "output"))
      (node (ref "R306") (pin "2") (pinfunction "2_2") (pintype "passive"))
      (node (ref "TP13") (pin "TP") (pinfunction "1_TP") (pintype "passive"))
    )
    (net (code "65") (name "Net-(J101-1)") (class "Default")
      (node (ref "C101") (pin "2") (pinfunction "2_2") (pintype "passive"))
      (node (ref "C102") (pin "2") (pinfunction "2_2") (pintype "passive"))
      (node (ref "C103") (pin "2") (pinfunction "2_2") (pintype "passive"))
      (node (ref "J101") (pin "C") (pinfunction "1_C") (pintype "passive"))
    )
    (net (code "66") (name "Net-(J102-1)") (class "Default")
      (node (ref "C118") (pin "2") (pinfunction "2_2") (pintype "passive"))
      (node (ref "C119") (pin "2") (pinfunction "2_2") (pintype "passive"))
      (node (ref "C120") (pin "2") (pinfunction "2_2") (pintype "passive"))
      (node (ref "J102") (pin "C") (pinfunction "1_C") (pintype "passive"))
    )
    (net (code "67") (name "Net-(J301-1)") (class "Default")
      (node (ref "J301") (pin "C") (pinfunction "1_C") (pintype "passive"))
      (node (ref "JP301") (pin "2") (pinfunction "2_2") (pintype "passive"))
      (node (ref "R302") (pin "1") (pinfunction "1_1") (pintype "passive"))
    )
    (net (code "68") (name "Net-(J301-GND1-PadG1)") (class "Default")
      (node (ref "J301") (pin "G1") (pinfunction "GND1_G1") (pintype "power_in"))
      (node (ref "J301") (pin "G2") (pinfunction "GND1_G2") (pintype "power_in"))
      (node (ref "J301") (pin "G3") (pinfunction "GND1_G3") (pintype "power_in"))
      (node (ref "J301") (pin "G4") (pinfunction "GND1_G4") (pintype "power_in"))
      (node (ref "JP301") (pin "1") (pinfunction "1_1") (pintype "passive"))
      (node (ref "R303") (pin "1") (pinfunction "1_1") (pintype "passive"))
    )
    (net (code "69") (name "Net-(J302-1)") (class "Default")
      (node (ref "J302") (pin "C") (pinfunction "1_C") (pintype "passive"))
      (node (ref "R304") (pin "1") (pinfunction "1_1") (pintype "passive"))
    )
    (net (code "70") (name "Net-(J402-Pad3)") (class "Default")
      (node (ref "J402") (pin "3") (pinfunction "3_3") (pintype "passive"))
      (node (ref "R408") (pin "2") (pinfunction "2_2") (pintype "passive"))
    )
    (net (code "71") (name "Net-(LED301-C)") (class "Default")
      (node (ref "LED301") (pin "K") (pinfunction "C_K") (pintype "passive"))
      (node (ref "R309") (pin "1") (pinfunction "1_1") (pintype "passive"))
    )
    (net (code "72") (name "Net-(LED401-C)") (class "Default")
      (node (ref "LED401") (pin "K") (pinfunction "C_K") (pintype "passive"))
      (node (ref "R406") (pin "1") (pinfunction "1_1") (pintype "passive"))
    )
    (net (code "73") (name "Net-(LED402-C)") (class "Default")
      (node (ref "LED402") (pin "K") (pinfunction "C_K") (pintype "passive"))
      (node (ref "R407") (pin "1") (pinfunction "1_1") (pintype "passive"))
    )
    (net (code "74") (name "Net-(R315-Pad2)") (class "Default")
      (node (ref "R315") (pin "2") (pinfunction "2_2") (pintype "passive"))
      (node (ref "R316") (pin "1") (pinfunction "1_1") (pintype "passive"))
      (node (ref "T301") (pin "B") (pinfunction "B_B") (pintype "passive"))
      (node (ref "T302") (pin "B") (pinfunction "B_B") (pintype "passive"))
    )
    (net (code "75") (name "Net-(T101-F1)") (class "Default")
      (node (ref "R101") (pin "1") (pinfunction "1_1") (pintype "passive"))
      (node (ref "T101") (pin "12") (pinfunction "F1_12") (pintype "passive"))
      (node (ref "T101") (pin "2") (pinfunction "S2_2") (pintype "passive"))
    )
    (net (code "76") (name "Net-(T101-F4)") (class "Default")
      (node (ref "T101") (pin "3") (pinfunction "S3_3") (pintype "passive"))
      (node (ref "T101") (pin "9") (pinfunction "F4_9") (pintype "passive"))
    )
    (net (code "77") (name "Net-(T101-F5)") (class "Default")
      (node (ref "C101") (pin "1") (pinfunction "1_1") (pintype "passive"))
      (node (ref "T101") (pin "4") (pinfunction "S4_4") (pintype "passive"))
      (node (ref "T101") (pin "8") (pinfunction "F5_8") (pintype "passive"))
    )
    (net (code "78") (name "Net-(T101-F6)") (class "Default")
      (node (ref "C102") (pin "1") (pinfunction "1_1") (pintype "passive"))
      (node (ref "T101") (pin "5") (pinfunction "S5_5") (pintype "passive"))
      (node (ref "T101") (pin "7") (pinfunction "F6_7") (pintype "passive"))
    )
    (net (code "79") (name "Net-(T101-S6)") (class "Default")
      (node (ref "C103") (pin "1") (pinfunction "1_1") (pintype "passive"))
      (node (ref "T101") (pin "6") (pinfunction "S6_6") (pintype "passive"))
    )
    (net (code "80") (name "Net-(T102-F1)") (class "Default")
      (node (ref "C119") (pin "1") (pinfunction "1_1") (pintype "passive"))
      (node (ref "T102") (pin "12") (pinfunction "F1_12") (pintype "passive"))
      (node (ref "T102") (pin "2") (pinfunction "S2_2") (pintype "passive"))
    )
    (net (code "81") (name "Net-(T102-F2)") (class "Default")
      (node (ref "C118") (pin "1") (pinfunction "1_1") (pintype "passive"))
      (node (ref "T102") (pin "11") (pinfunction "F2_11") (pintype "passive"))
      (node (ref "T102") (pin "3") (pinfunction "S3_3") (pintype "passive"))
    )
    (net (code "82") (name "Net-(T102-F3)") (class "Default")
      (node (ref "T102") (pin "10") (pinfunction "F3_10") (pintype "passive"))
      (node (ref "T102") (pin "4") (pinfunction "S4_4") (pintype "passive"))
    )
    (net (code "83") (name "Net-(T102-F6)") (class "Default")
      (node (ref "R132") (pin "2") (pinfunction "2_2") (pintype "passive"))
      (node (ref "T102") (pin "5") (pinfunction "S5_5") (pintype "passive"))
      (node (ref "T102") (pin "7") (pinfunction "F6_7") (pintype "passive"))
    )
    (net (code "84") (name "Net-(T102-S1)") (class "Default")
      (node (ref "C120") (pin "1") (pinfunction "1_1") (pintype "passive"))
      (node (ref "T102") (pin "1") (pinfunction "S1_1") (pintype "passive"))
    )
    (net (code "85") (name "Net-(X401A-KL)") (class "Default")
      (node (ref "J401") (pin "1") (pinfunction "1_1") (pintype "passive"))
      (node (ref "X401") (pin "1") (pinfunction "KL_1") (pintype "passive"))
    )
    (net (code "86") (name "VB") (class "Default")
      (node (ref "C116") (pin "1") (pinfunction "1_1") (pintype "passive"))
      (node (ref "C117") (pin "1") (pinfunction "1_1") (pintype "passive"))
      (node (ref "C408") (pin "1") (pinfunction "1_1") (pintype "passive"))
      (node (ref "C411") (pin "1") (pinfunction "1_1") (pintype "passive"))
      (node (ref "C412") (pin "1") (pinfunction "1_1") (pintype "passive"))
      (node (ref "C413") (pin "1") (pinfunction "1_1") (pintype "passive"))
      (node (ref "L103") (pin "2") (pinfunction "2_2") (pintype "passive"))
      (node (ref "L104") (pin "2") (pinfunction "2_2") (pintype "passive"))
      (node (ref "L402") (pin "2") (pinfunction "2_2") (pintype "passive"))
      (node (ref "R132") (pin "1") (pinfunction "1_1") (pintype "passive"))
      (node (ref "R404") (pin "2") (pinfunction "2_2") (pintype "passive"))
      (node (ref "R405") (pin "2") (pinfunction "2_2") (pintype "passive"))
    )
    (net (code "87") (name "unconnected-(J402-Pad4)") (class "Default")
      (node (ref "J402") (pin "4") (pinfunction "4_4") (pintype "passive"))
    )
  )
)
